# MainMaster.net
KiCad netlist of a schematic drawn in Altium Designer
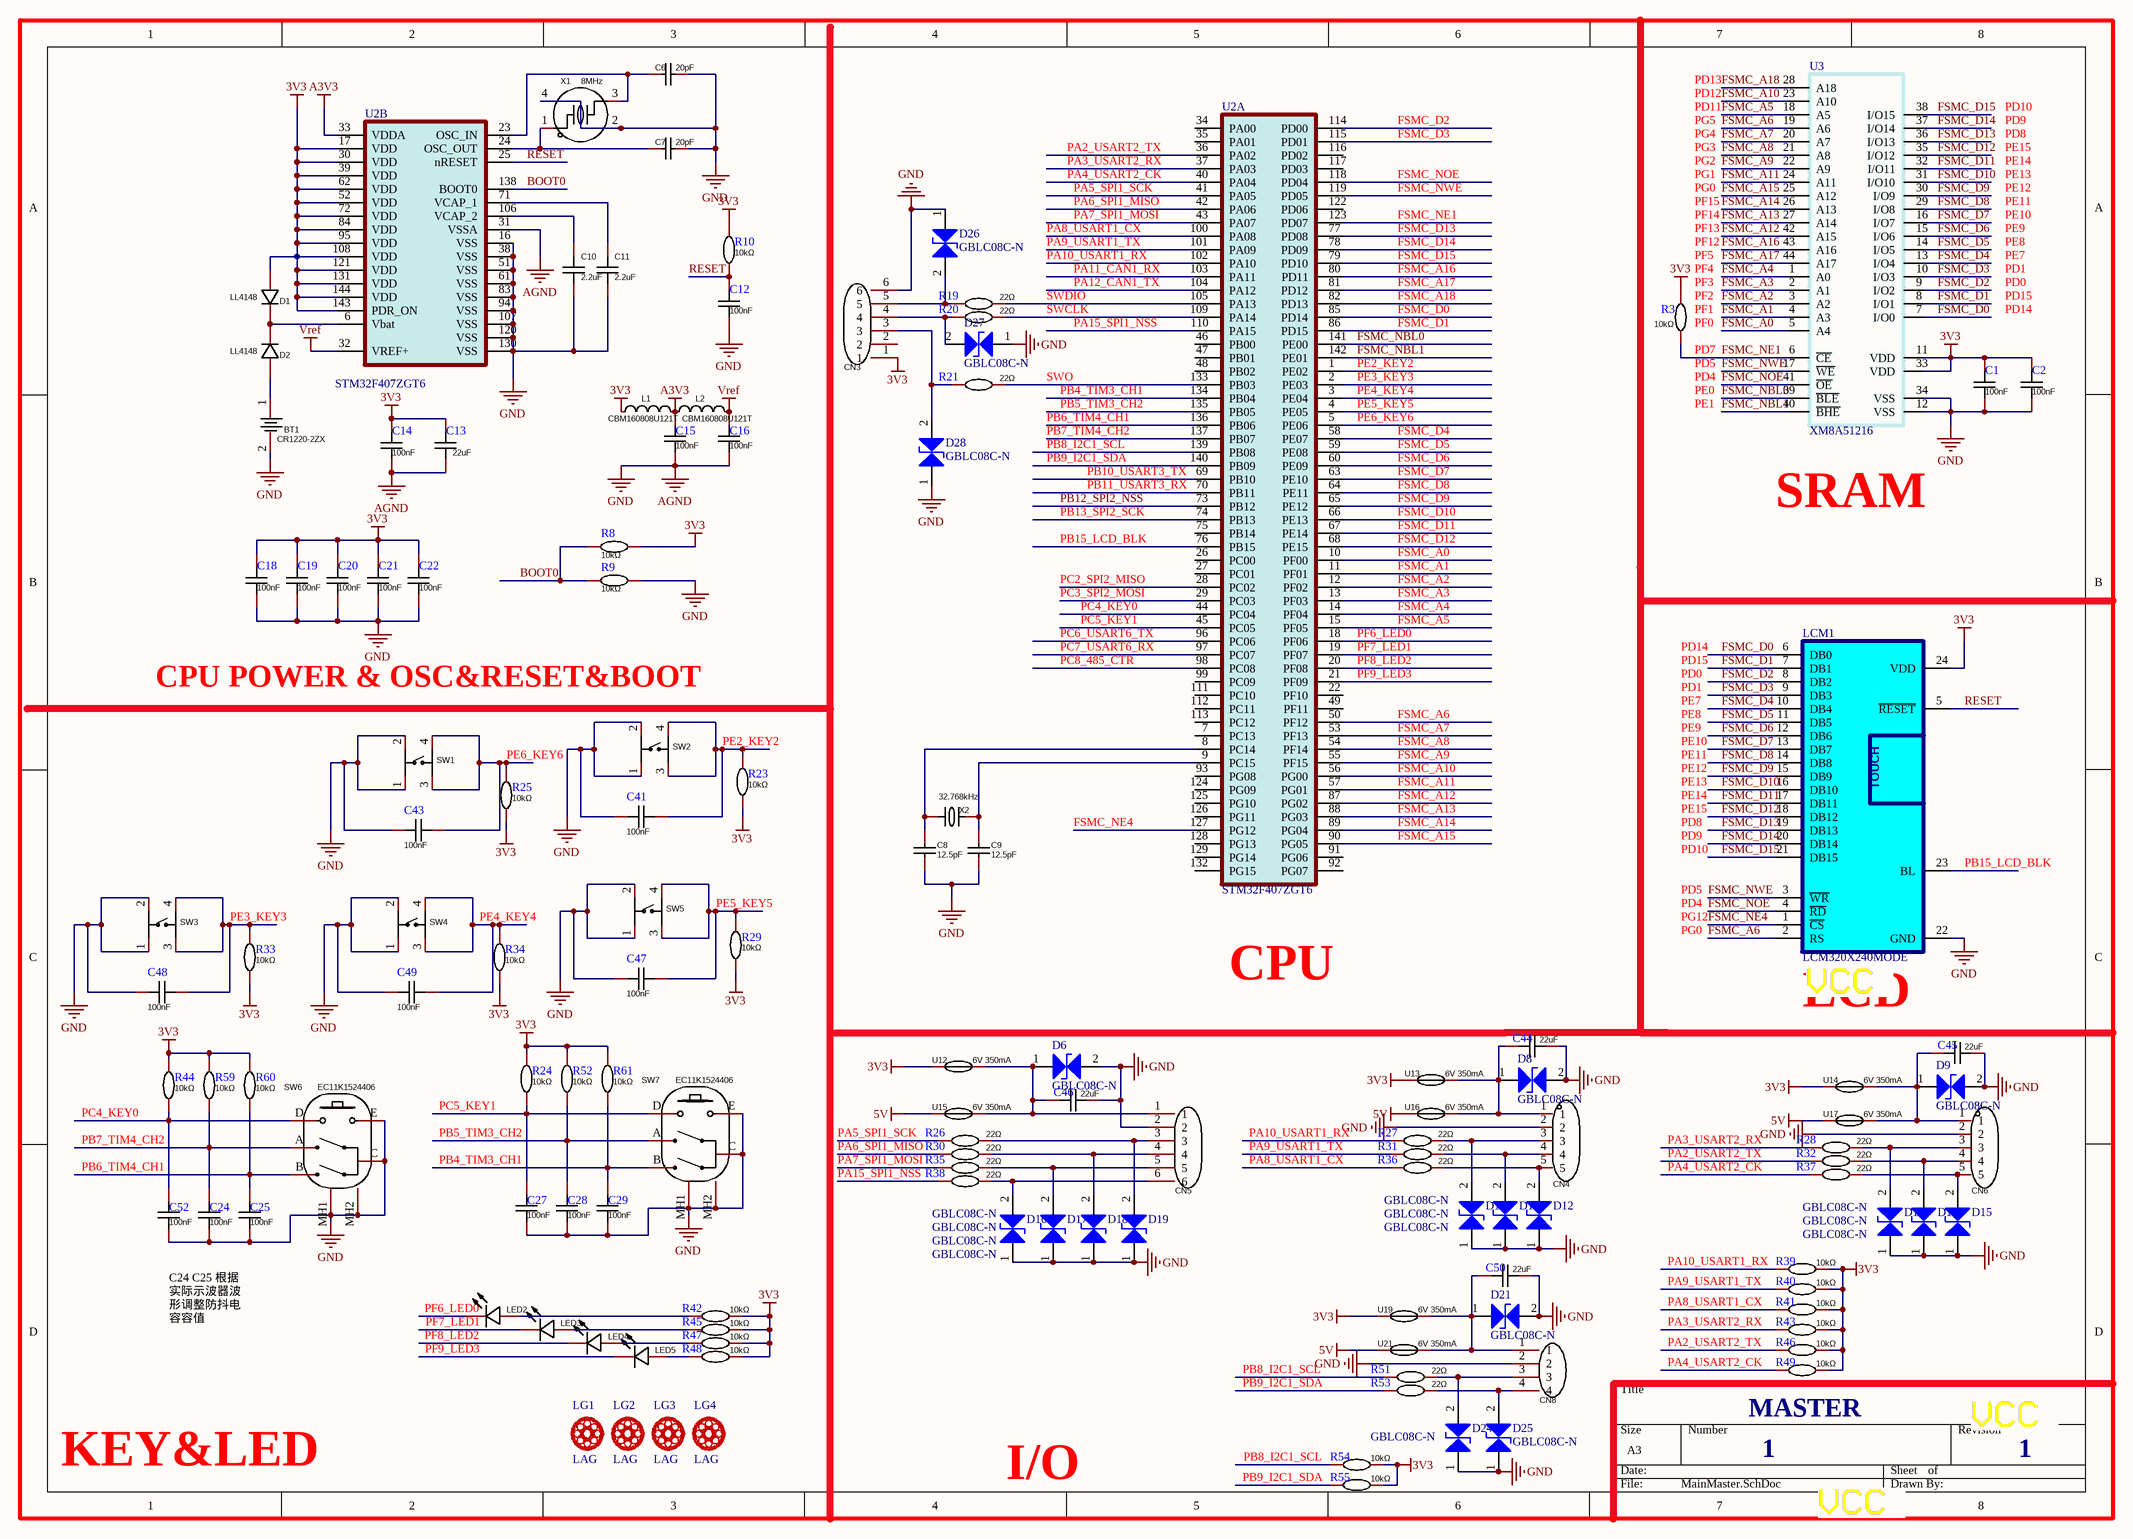
[diagram p0: MainMaster.SchDoc]

(export (version "E")
  (design (tool "Eeschema 10.0.6"))
  (components
    (comp (ref "BT1")
      (value "CR1220-2ZX")
      (footprint "LI1220_1")
      (fields (field (name "NAME") "CR1220-2ZX") (field (name "MANUFACTURER") "Q&J"))
      (libsource (lib "altium-import") (part "root_3_CR1220-2ZX_"))
    )
    (comp (ref "C1")
      (value "CC0603KRX7R9BB104")
      (footprint "C0603")
      (fields
        (field (name "NAME") "100nF")
        (field (name "MANUFACTURER") "YAGEO(国巨)")
        (field (name "TOLERANCE") "±10%")
      )
      (libsource (lib "altium-import") (part "root_1_CC0603KRX7R9BB104_"))
    )
    (comp (ref "C2")
      (value "CC0603KRX7R9BB104")
      (footprint "C0603")
      (fields
        (field (name "NAME") "100nF")
        (field (name "MANUFACTURER") "YAGEO(国巨)")
        (field (name "TOLERANCE") "±10%")
      )
      (libsource (lib "altium-import") (part "root_1_CC0603KRX7R9BB104_"))
    )
    (comp (ref "C6")
      (value "CC0603JRNPO9BN200")
      (footprint "C0603")
      (fields
        (field (name "NAME") "20pF")
        (field (name "MANUFACTURER") "YAGEO(国巨)")
        (field (name "TOLERANCE") "±5%")
      )
      (libsource (lib "altium-import") (part "root_0_CC0603JRNPO9BN200_"))
    )
    (comp (ref "C7")
      (value "CC0603JRNPO9BN200")
      (footprint "C0603")
      (fields
        (field (name "NAME") "20pF")
        (field (name "MANUFACTURER") "YAGEO(国巨)")
        (field (name "TOLERANCE") "±5%")
      )
      (libsource (lib "altium-import") (part "root_0_CC0603JRNPO9BN200_"))
    )
    (comp (ref "C8")
      (value "CC0603JRNPO9BN200")
      (footprint "C0603")
      (fields
        (field (name "NAME") "12.5pF")
        (field (name "MANUFACTURER") "YAGEO(国巨)")
        (field (name "TOLERANCE") "±5%")
      )
      (libsource (lib "altium-import") (part "root_1_CC0603JRNPO9BN200_"))
    )
    (comp (ref "C9")
      (value "CC0603JRNPO9BN200")
      (footprint "C0603")
      (fields
        (field (name "NAME") "12.5pF")
        (field (name "MANUFACTURER") "YAGEO(国巨)")
        (field (name "TOLERANCE") "±5%")
      )
      (libsource (lib "altium-import") (part "root_1_CC0603JRNPO9BN200_"))
    )
    (comp (ref "C10")
      (value "CL10A225KA8NNNC")
      (footprint "C0603")
      (fields
        (field (name "NAME") "2.2uF")
        (field (name "MANUFACTURER") "SAMSUNG(三星)")
        (field (name "TOLERANCE") "±10%")
      )
      (libsource (lib "altium-import") (part "root_1_CL10A225KA8NNNC_"))
    )
    (comp (ref "C11")
      (value "CL10A225KA8NNNC")
      (footprint "C0603")
      (fields
        (field (name "NAME") "2.2uF")
        (field (name "MANUFACTURER") "SAMSUNG(三星)")
        (field (name "TOLERANCE") "±10%")
      )
      (libsource (lib "altium-import") (part "root_1_CL10A225KA8NNNC_"))
    )
    (comp (ref "C12")
      (value "CC0603KRX7R9BB104")
      (footprint "C0603")
      (fields
        (field (name "NAME") "100nF")
        (field (name "MANUFACTURER") "YAGEO(国巨)")
        (field (name "TOLERANCE") "±10%")
      )
      (libsource (lib "altium-import") (part "root_1_CC0603KRX7R9BB104_"))
    )
    (comp (ref "C13")
      (value "CC0603KRX7R9BB104")
      (footprint "C1210")
      (fields
        (field (name "NAME") "22uF")
        (field (name "MANUFACTURER") "YAGEO(国巨)")
        (field (name "TOLERANCE") "±10%")
      )
      (libsource (lib "altium-import") (part "root_1_CC0603KRX7R9BB104_"))
    )
    (comp (ref "C14")
      (value "CC0603KRX7R9BB104")
      (footprint "C0603")
      (fields
        (field (name "NAME") "100nF")
        (field (name "MANUFACTURER") "YAGEO(国巨)")
        (field (name "TOLERANCE") "±10%")
      )
      (libsource (lib "altium-import") (part "root_1_CC0603KRX7R9BB104_"))
    )
    (comp (ref "C15")
      (value "CC0603KRX7R9BB104")
      (footprint "C0603")
      (fields
        (field (name "NAME") "100nF")
        (field (name "MANUFACTURER") "YAGEO(国巨)")
        (field (name "TOLERANCE") "±10%")
      )
      (libsource (lib "altium-import") (part "root_1_CC0603KRX7R9BB104_"))
    )
    (comp (ref "C16")
      (value "CC0603KRX7R9BB104")
      (footprint "C0603")
      (fields
        (field (name "NAME") "100nF")
        (field (name "MANUFACTURER") "YAGEO(国巨)")
        (field (name "TOLERANCE") "±10%")
      )
      (libsource (lib "altium-import") (part "root_1_CC0603KRX7R9BB104_"))
    )
    (comp (ref "C18")
      (value "CC0603KRX7R9BB104")
      (footprint "C0603")
      (fields
        (field (name "NAME") "100nF")
        (field (name "MANUFACTURER") "YAGEO(国巨)")
        (field (name "TOLERANCE") "±10%")
      )
      (libsource (lib "altium-import") (part "root_1_CC0603KRX7R9BB104_"))
    )
    (comp (ref "C19")
      (value "CC0603KRX7R9BB104")
      (footprint "C0603")
      (fields
        (field (name "NAME") "100nF")
        (field (name "MANUFACTURER") "YAGEO(国巨)")
        (field (name "TOLERANCE") "±10%")
      )
      (libsource (lib "altium-import") (part "root_1_CC0603KRX7R9BB104_"))
    )
    (comp (ref "C20")
      (value "CC0603KRX7R9BB104")
      (footprint "C0603")
      (fields
        (field (name "NAME") "100nF")
        (field (name "MANUFACTURER") "YAGEO(国巨)")
        (field (name "TOLERANCE") "±10%")
      )
      (libsource (lib "altium-import") (part "root_1_CC0603KRX7R9BB104_"))
    )
    (comp (ref "C21")
      (value "CC0603KRX7R9BB104")
      (footprint "C0603")
      (fields
        (field (name "NAME") "100nF")
        (field (name "MANUFACTURER") "YAGEO(国巨)")
        (field (name "TOLERANCE") "±10%")
      )
      (libsource (lib "altium-import") (part "root_1_CC0603KRX7R9BB104_"))
    )
    (comp (ref "C22")
      (value "CC0603KRX7R9BB104")
      (footprint "C0603")
      (fields
        (field (name "NAME") "100nF")
        (field (name "MANUFACTURER") "YAGEO(国巨)")
        (field (name "TOLERANCE") "±10%")
      )
      (libsource (lib "altium-import") (part "root_1_CC0603KRX7R9BB104_"))
    )
    (comp (ref "C24")
      (value "CC0603KRX7R9BB104")
      (footprint "C0603")
      (fields
        (field (name "NAME") "100nF")
        (field (name "MANUFACTURER") "YAGEO(国巨)")
        (field (name "TOLERANCE") "±10%")
      )
      (libsource (lib "altium-import") (part "root_3_CC0603KRX7R9BB104_"))
    )
    (comp (ref "C25")
      (value "CC0603KRX7R9BB104")
      (footprint "C0603")
      (fields
        (field (name "NAME") "100nF")
        (field (name "MANUFACTURER") "YAGEO(国巨)")
        (field (name "TOLERANCE") "±10%")
      )
      (libsource (lib "altium-import") (part "root_3_CC0603KRX7R9BB104_"))
    )
    (comp (ref "C27")
      (value "CC0603KRX7R9BB104")
      (footprint "C0603")
      (fields
        (field (name "NAME") "100nF")
        (field (name "MANUFACTURER") "YAGEO(国巨)")
        (field (name "TOLERANCE") "±10%")
      )
      (libsource (lib "altium-import") (part "root_3_CC0603KRX7R9BB104_"))
    )
    (comp (ref "C28")
      (value "CC0603KRX7R9BB104")
      (footprint "C0603")
      (fields
        (field (name "NAME") "100nF")
        (field (name "MANUFACTURER") "YAGEO(国巨)")
        (field (name "TOLERANCE") "±10%")
      )
      (libsource (lib "altium-import") (part "root_3_CC0603KRX7R9BB104_"))
    )
    (comp (ref "C29")
      (value "CC0603KRX7R9BB104")
      (footprint "C0603")
      (fields
        (field (name "NAME") "100nF")
        (field (name "MANUFACTURER") "YAGEO(国巨)")
        (field (name "TOLERANCE") "±10%")
      )
      (libsource (lib "altium-import") (part "root_3_CC0603KRX7R9BB104_"))
    )
    (comp (ref "C41")
      (value "CC0603KRX7R9BB104")
      (footprint "C0603")
      (fields
        (field (name "NAME") "100nF")
        (field (name "MANUFACTURER") "YAGEO(国巨)")
        (field (name "TOLERANCE") "±10%")
      )
      (libsource (lib "altium-import") (part "root_2_CC0603KRX7R9BB104_"))
    )
    (comp (ref "C43")
      (value "CC0603KRX7R9BB104")
      (footprint "C0603")
      (fields
        (field (name "NAME") "100nF")
        (field (name "MANUFACTURER") "YAGEO(国巨)")
        (field (name "TOLERANCE") "±10%")
      )
      (libsource (lib "altium-import") (part "root_2_CC0603KRX7R9BB104_"))
    )
    (comp (ref "C44")
      (value "CC0603KRX7R9BB104")
      (footprint "C1210")
      (fields
        (field (name "NAME") "22uF")
        (field (name "MANUFACTURER") "YAGEO(国巨)")
        (field (name "TOLERANCE") "±10%")
      )
      (libsource (lib "altium-import") (part "root_2_CC0603KRX7R9BB104_"))
    )
    (comp (ref "C45")
      (value "CC0603KRX7R9BB104")
      (footprint "C1210")
      (fields
        (field (name "NAME") "22uF")
        (field (name "MANUFACTURER") "YAGEO(国巨)")
        (field (name "TOLERANCE") "±10%")
      )
      (libsource (lib "altium-import") (part "root_2_CC0603KRX7R9BB104_"))
    )
    (comp (ref "C46")
      (value "CC0603KRX7R9BB104")
      (footprint "C1210")
      (fields
        (field (name "NAME") "22uF")
        (field (name "MANUFACTURER") "YAGEO(国巨)")
        (field (name "TOLERANCE") "±10%")
      )
      (libsource (lib "altium-import") (part "root_2_CC0603KRX7R9BB104_"))
    )
    (comp (ref "C47")
      (value "CC0603KRX7R9BB104")
      (footprint "C0603")
      (fields
        (field (name "NAME") "100nF")
        (field (name "MANUFACTURER") "YAGEO(国巨)")
        (field (name "TOLERANCE") "±10%")
      )
      (libsource (lib "altium-import") (part "root_2_CC0603KRX7R9BB104_"))
    )
    (comp (ref "C48")
      (value "CC0603KRX7R9BB104")
      (footprint "C0603")
      (fields
        (field (name "NAME") "100nF")
        (field (name "MANUFACTURER") "YAGEO(国巨)")
        (field (name "TOLERANCE") "±10%")
      )
      (libsource (lib "altium-import") (part "root_2_CC0603KRX7R9BB104_"))
    )
    (comp (ref "C49")
      (value "CC0603KRX7R9BB104")
      (footprint "C0603")
      (fields
        (field (name "NAME") "100nF")
        (field (name "MANUFACTURER") "YAGEO(国巨)")
        (field (name "TOLERANCE") "±10%")
      )
      (libsource (lib "altium-import") (part "root_2_CC0603KRX7R9BB104_"))
    )
    (comp (ref "C50")
      (value "CC0603KRX7R9BB104")
      (footprint "C1210")
      (fields
        (field (name "NAME") "22uF")
        (field (name "MANUFACTURER") "YAGEO(国巨)")
        (field (name "TOLERANCE") "±10%")
      )
      (libsource (lib "altium-import") (part "root_2_CC0603KRX7R9BB104_"))
    )
    (comp (ref "C52")
      (value "CC0603KRX7R9BB104")
      (footprint "C0603")
      (fields
        (field (name "NAME") "100nF")
        (field (name "MANUFACTURER") "YAGEO(国巨)")
        (field (name "TOLERANCE") "±10%")
      )
      (libsource (lib "altium-import") (part "root_3_CC0603KRX7R9BB104_"))
    )
    (comp (ref "CN3")
      (value "XH-6A")
      (footprint "XH2.5-6P")
      (fields (field (name "MANUFACTURER") "BOOMELE(博穆精密)"))
      (libsource (lib "altium-import") (part "root_2_mirrored_XH-6A_"))
    )
    (comp (ref "CN4")
      (value "XH-5A")
      (footprint "XH2.5-5P")
      (fields (field (name "MANUFACTURER") "BOOMELE(博穆精密)"))
      (libsource (lib "altium-import") (part "root_0_XH-5A_"))
    )
    (comp (ref "CN5")
      (value "XH-6A")
      (footprint "XH2.5-6P")
      (fields (field (name "MANUFACTURER") "BOOMELE(博穆精密)"))
      (libsource (lib "altium-import") (part "root_0_mirrored_XH-6A_"))
    )
    (comp (ref "CN6")
      (value "XH-5A")
      (footprint "XH2.5-5P")
      (fields (field (name "MANUFACTURER") "BOOMELE(博穆精密)"))
      (libsource (lib "altium-import") (part "root_0_XH-5A_"))
    )
    (comp (ref "CN8")
      (value "XH-4A")
      (footprint "XH2.5-4P")
      (fields (field (name "MANUFACTURER") "BOOMELE(博穆精密)"))
      (libsource (lib "altium-import") (part "root_0_mirrored_XH-4A_"))
    )
    (comp (ref "D1")
      (value "LL4148_C84135")
      (footprint "MINI_MELF (LL34)")
      (fields
        (field (name "NAME") "LL4148")
        (field (name "MANUFACTURER") "onsemi(安森美)")
        (field (name "MANUFACTURER PART") "LL4148")
      )
      (libsource (lib "altium-import") (part "root_1_LL4148_C84135_"))
    )
    (comp (ref "D2")
      (value "LL4148_C84135")
      (footprint "MINI_MELF (LL34)")
      (fields
        (field (name "NAME") "LL4148")
        (field (name "MANUFACTURER") "onsemi(安森美)")
        (field (name "MANUFACTURER PART") "LL4148")
      )
      (libsource (lib "altium-import") (part "root_3_LL4148_C84135_"))
    )
    (comp (ref "D6")
      (value "GBLC08C-N")
      (footprint "SOD-323_L1.8-W1.3-LS2.5-BI")
      (description "LXES1UTAA1-157,0402,MURATA")
      (fields (field (name "NAME") "GBLC08C-N") (field (name "MANUFACTURER") "BORN伯恩半导体"))
      (libsource (lib "ErpMaterialData-U9") (part "DIODE ZENER2"))
    )
    (comp (ref "D8")
      (value "GBLC08C-N")
      (footprint "SOD-323_L1.8-W1.3-LS2.5-BI")
      (description "LXES1UTAA1-157,0402,MURATA")
      (fields (field (name "NAME") "GBLC08C-N") (field (name "MANUFACTURER") "BORN伯恩半导体"))
      (libsource (lib "ErpMaterialData-U9") (part "DIODE ZENER2"))
    )
    (comp (ref "D9")
      (value "GBLC08C-N")
      (footprint "SOD-323_L1.8-W1.3-LS2.5-BI")
      (description "LXES1UTAA1-157,0402,MURATA")
      (fields (field (name "NAME") "GBLC08C-N") (field (name "MANUFACTURER") "BORN伯恩半导体"))
      (libsource (lib "ErpMaterialData-U9") (part "DIODE ZENER2"))
    )
    (comp (ref "D10")
      (value "GBLC08C-N")
      (footprint "SOD-323_L1.8-W1.3-LS2.5-BI")
      (description "LXES1UTAA1-157,0402,MURATA")
      (fields (field (name "NAME") "GBLC08C-N") (field (name "MANUFACTURER") "BORN伯恩半导体"))
      (libsource (lib "ErpMaterialData-U9") (part "DIODE ZENER2"))
    )
    (comp (ref "D11")
      (value "GBLC08C-N")
      (footprint "SOD-323_L1.8-W1.3-LS2.5-BI")
      (description "LXES1UTAA1-157,0402,MURATA")
      (fields (field (name "NAME") "GBLC08C-N") (field (name "MANUFACTURER") "BORN伯恩半导体"))
      (libsource (lib "ErpMaterialData-U9") (part "DIODE ZENER2"))
    )
    (comp (ref "D12")
      (value "GBLC08C-N")
      (footprint "SOD-323_L1.8-W1.3-LS2.5-BI")
      (description "LXES1UTAA1-157,0402,MURATA")
      (fields (field (name "NAME") "GBLC08C-N") (field (name "MANUFACTURER") "BORN伯恩半导体"))
      (libsource (lib "ErpMaterialData-U9") (part "DIODE ZENER2"))
    )
    (comp (ref "D13")
      (value "GBLC08C-N")
      (footprint "SOD-323_L1.8-W1.3-LS2.5-BI")
      (description "LXES1UTAA1-157,0402,MURATA")
      (fields (field (name "NAME") "GBLC08C-N") (field (name "MANUFACTURER") "BORN伯恩半导体"))
      (libsource (lib "ErpMaterialData-U9") (part "DIODE ZENER2"))
    )
    (comp (ref "D14")
      (value "GBLC08C-N")
      (footprint "SOD-323_L1.8-W1.3-LS2.5-BI")
      (description "LXES1UTAA1-157,0402,MURATA")
      (fields (field (name "NAME") "GBLC08C-N") (field (name "MANUFACTURER") "BORN伯恩半导体"))
      (libsource (lib "ErpMaterialData-U9") (part "DIODE ZENER2"))
    )
    (comp (ref "D15")
      (value "GBLC08C-N")
      (footprint "SOD-323_L1.8-W1.3-LS2.5-BI")
      (description "LXES1UTAA1-157,0402,MURATA")
      (fields (field (name "NAME") "GBLC08C-N") (field (name "MANUFACTURER") "BORN伯恩半导体"))
      (libsource (lib "ErpMaterialData-U9") (part "DIODE ZENER2"))
    )
    (comp (ref "D16")
      (value "GBLC08C-N")
      (footprint "SOD-323_L1.8-W1.3-LS2.5-BI")
      (description "LXES1UTAA1-157,0402,MURATA")
      (fields (field (name "NAME") "GBLC08C-N") (field (name "MANUFACTURER") "BORN伯恩半导体"))
      (libsource (lib "ErpMaterialData-U9") (part "DIODE ZENER2"))
    )
    (comp (ref "D17")
      (value "GBLC08C-N")
      (footprint "SOD-323_L1.8-W1.3-LS2.5-BI")
      (description "LXES1UTAA1-157,0402,MURATA")
      (fields (field (name "NAME") "GBLC08C-N") (field (name "MANUFACTURER") "BORN伯恩半导体"))
      (libsource (lib "ErpMaterialData-U9") (part "DIODE ZENER2"))
    )
    (comp (ref "D18")
      (value "GBLC08C-N")
      (footprint "SOD-323_L1.8-W1.3-LS2.5-BI")
      (description "LXES1UTAA1-157,0402,MURATA")
      (fields (field (name "NAME") "GBLC08C-N") (field (name "MANUFACTURER") "BORN伯恩半导体"))
      (libsource (lib "ErpMaterialData-U9") (part "DIODE ZENER2"))
    )
    (comp (ref "D19")
      (value "GBLC08C-N")
      (footprint "SOD-323_L1.8-W1.3-LS2.5-BI")
      (description "LXES1UTAA1-157,0402,MURATA")
      (fields (field (name "NAME") "GBLC08C-N") (field (name "MANUFACTURER") "BORN伯恩半导体"))
      (libsource (lib "ErpMaterialData-U9") (part "DIODE ZENER2"))
    )
    (comp (ref "D21")
      (value "GBLC08C-N")
      (footprint "SOD-323_L1.8-W1.3-LS2.5-BI")
      (description "LXES1UTAA1-157,0402,MURATA")
      (fields (field (name "NAME") "GBLC08C-N") (field (name "MANUFACTURER") "BORN伯恩半导体"))
      (libsource (lib "ErpMaterialData-U9") (part "DIODE ZENER2"))
    )
    (comp (ref "D24")
      (value "GBLC08C-N")
      (footprint "SOD-323_L1.8-W1.3-LS2.5-BI")
      (description "LXES1UTAA1-157,0402,MURATA")
      (fields (field (name "NAME") "GBLC08C-N") (field (name "MANUFACTURER") "BORN伯恩半导体"))
      (libsource (lib "ErpMaterialData-U9") (part "DIODE ZENER2"))
    )
    (comp (ref "D25")
      (value "GBLC08C-N")
      (footprint "SOD-323_L1.8-W1.3-LS2.5-BI")
      (description "LXES1UTAA1-157,0402,MURATA")
      (fields (field (name "NAME") "GBLC08C-N") (field (name "MANUFACTURER") "BORN伯恩半导体"))
      (libsource (lib "ErpMaterialData-U9") (part "DIODE ZENER2"))
    )
    (comp (ref "D26")
      (value "GBLC08C-N")
      (footprint "SOD-323_L1.8-W1.3-LS2.5-BI")
      (description "LXES1UTAA1-157,0402,MURATA")
      (fields (field (name "NAME") "GBLC08C-N") (field (name "MANUFACTURER") "BORN伯恩半导体"))
      (libsource (lib "ErpMaterialData-U9") (part "DIODE ZENER2"))
    )
    (comp (ref "D27")
      (value "GBLC08C-N")
      (footprint "SOD-323_L1.8-W1.3-LS2.5-BI")
      (description "LXES1UTAA1-157,0402,MURATA")
      (fields (field (name "NAME") "GBLC08C-N") (field (name "MANUFACTURER") "BORN伯恩半导体"))
      (libsource (lib "ErpMaterialData-U9") (part "DIODE ZENER2"))
    )
    (comp (ref "D28")
      (value "GBLC08C-N")
      (footprint "SOD-323_L1.8-W1.3-LS2.5-BI")
      (description "LXES1UTAA1-157,0402,MURATA")
      (fields (field (name "NAME") "GBLC08C-N") (field (name "MANUFACTURER") "BORN伯恩半导体"))
      (libsource (lib "ErpMaterialData-U9") (part "DIODE ZENER2"))
    )
    (comp (ref "L1")
      (value "CBM160808U121T")
      (footprint "L0603")
      (fields
        (field (name "NAME") "CBM160808U121T")
        (field (name "MANUFACTURER") "FH(风华)")
        (field (name "TOLERANCE") "±25%")
      )
      (libsource (lib "altium-import") (part "root_0_CBM160808U121T_"))
    )
    (comp (ref "L2")
      (value "CBM160808U121T")
      (footprint "L0603")
      (fields
        (field (name "NAME") "CBM160808U121T")
        (field (name "MANUFACTURER") "FH(风华)")
        (field (name "TOLERANCE") "±25%")
      )
      (libsource (lib "altium-import") (part "root_0_CBM160808U121T_"))
    )
    (comp (ref "LCM1")
      (value "LCM320X240MODE")
      (footprint "LCM2.8 MODE")
      (libsource (lib "华南师范控制板") (part "LCM320X240MODE"))
    )
    (comp (ref "LED2")
      (value "17-21SYGC/S530-E3/TR8")
      (footprint "LED 0805G")
      (fields (field (name "MANUFACTURER") "EVERLIGHT(亿光)"))
      (libsource (lib "altium-import") (part "root_0_17-21SYGC/S530-E3/TR8_"))
    )
    (comp (ref "LED3")
      (value "17-21SYGC/S530-E3/TR8")
      (footprint "LED 0805G")
      (fields (field (name "MANUFACTURER") "EVERLIGHT(亿光)"))
      (libsource (lib "altium-import") (part "root_0_17-21SYGC/S530-E3/TR8_"))
    )
    (comp (ref "LED4")
      (value "17-21SYGC/S530-E3/TR8")
      (footprint "LED 0805G")
      (fields (field (name "MANUFACTURER") "EVERLIGHT(亿光)"))
      (libsource (lib "altium-import") (part "root_0_17-21SYGC/S530-E3/TR8_"))
    )
    (comp (ref "LED5")
      (value "17-21SYGC/S530-E3/TR8")
      (footprint "LED 0805G")
      (fields (field (name "MANUFACTURER") "EVERLIGHT(亿光)"))
      (libsource (lib "altium-import") (part "root_0_17-21SYGC/S530-E3/TR8_"))
    )
    (comp (ref "LG1") (value "LAG") (footprint "LAGVAL") (libsource (lib "3DGeneral") (part "LAGVAL")))
    (comp (ref "LG2") (value "LAG") (footprint "LAGVAL") (libsource (lib "3DGeneral") (part "LAGVAL")))
    (comp (ref "LG3") (value "LAG") (footprint "LAGVAL") (libsource (lib "3DGeneral") (part "LAGVAL")))
    (comp (ref "LG4") (value "LAG") (footprint "LAGVAL") (libsource (lib "3DGeneral") (part "LAGVAL")))
    (comp (ref "R3")
      (value "10kΩ")
      (footprint "R0603")
      (fields
        (field (name "MANUFACTURER") "UNI-ROYAL(厚声)")
        (field (name "MANUFACTURER PART") "0603WAF5113T5E")
        (field (name "TOLERANCE") "±1%")
      )
      (libsource (lib "altium-import") (part "root_1_0603WAF5113T5E_"))
    )
    (comp (ref "R8")
      (value "10kΩ")
      (footprint "R0603")
      (fields
        (field (name "MANUFACTURER") "UNI-ROYAL(厚声)")
        (field (name "MANUFACTURER PART") "0603WAF5113T5E")
        (field (name "TOLERANCE") "±1%")
      )
      (libsource (lib "altium-import") (part "root_0_0603WAF5113T5E_"))
    )
    (comp (ref "R9")
      (value "10kΩ")
      (footprint "R0603")
      (fields
        (field (name "MANUFACTURER") "UNI-ROYAL(厚声)")
        (field (name "MANUFACTURER PART") "0603WAF5113T5E")
        (field (name "TOLERANCE") "±1%")
      )
      (libsource (lib "altium-import") (part "root_0_0603WAF5113T5E_"))
    )
    (comp (ref "R10")
      (value "10kΩ")
      (footprint "R0603")
      (fields
        (field (name "MANUFACTURER") "UNI-ROYAL(厚声)")
        (field (name "MANUFACTURER PART") "0603WAF5113T5E")
        (field (name "TOLERANCE") "±1%")
      )
      (libsource (lib "altium-import") (part "root_3_0603WAF5113T5E_"))
    )
    (comp (ref "R19")
      (value "22Ω")
      (footprint "R0603")
      (fields
        (field (name "MANUFACTURER") "UNI-ROYAL(厚声)")
        (field (name "MANUFACTURER PART") "0603WAF5113T5E")
        (field (name "TOLERANCE") "±1%")
      )
      (libsource (lib "altium-import") (part "root_2_0603WAF5113T5E_"))
    )
    (comp (ref "R20")
      (value "22Ω")
      (footprint "R0603")
      (fields
        (field (name "MANUFACTURER") "UNI-ROYAL(厚声)")
        (field (name "MANUFACTURER PART") "0603WAF5113T5E")
        (field (name "TOLERANCE") "±1%")
      )
      (libsource (lib "altium-import") (part "root_2_0603WAF5113T5E_"))
    )
    (comp (ref "R21")
      (value "22Ω")
      (footprint "R0603")
      (fields
        (field (name "MANUFACTURER") "UNI-ROYAL(厚声)")
        (field (name "MANUFACTURER PART") "0603WAF5113T5E")
        (field (name "TOLERANCE") "±1%")
      )
      (libsource (lib "altium-import") (part "root_2_0603WAF5113T5E_"))
    )
    (comp (ref "R23")
      (value "10kΩ")
      (footprint "R0603")
      (fields
        (field (name "MANUFACTURER") "UNI-ROYAL(厚声)")
        (field (name "MANUFACTURER PART") "0603WAF5113T5E")
        (field (name "TOLERANCE") "±1%")
      )
      (libsource (lib "altium-import") (part "root_1_0603WAF5113T5E_"))
    )
    (comp (ref "R24")
      (value "10kΩ")
      (footprint "R0603")
      (fields
        (field (name "MANUFACTURER") "UNI-ROYAL(厚声)")
        (field (name "MANUFACTURER PART") "0603WAF5113T5E")
        (field (name "TOLERANCE") "±1%")
      )
      (libsource (lib "altium-import") (part "root_1_0603WAF5113T5E_"))
    )
    (comp (ref "R25")
      (value "10kΩ")
      (footprint "R0603")
      (fields
        (field (name "MANUFACTURER") "UNI-ROYAL(厚声)")
        (field (name "MANUFACTURER PART") "0603WAF5113T5E")
        (field (name "TOLERANCE") "±1%")
      )
      (libsource (lib "altium-import") (part "root_1_0603WAF5113T5E_"))
    )
    (comp (ref "R26")
      (value "22Ω")
      (footprint "R0603")
      (fields
        (field (name "MANUFACTURER") "UNI-ROYAL(厚声)")
        (field (name "MANUFACTURER PART") "0603WAF5113T5E")
        (field (name "TOLERANCE") "±1%")
      )
      (libsource (lib "altium-import") (part "root_2_0603WAF5113T5E_"))
    )
    (comp (ref "R27")
      (value "22Ω")
      (footprint "R0603")
      (fields
        (field (name "MANUFACTURER") "UNI-ROYAL(厚声)")
        (field (name "MANUFACTURER PART") "0603WAF5113T5E")
        (field (name "TOLERANCE") "±1%")
      )
      (libsource (lib "altium-import") (part "root_2_0603WAF5113T5E_"))
    )
    (comp (ref "R28")
      (value "22Ω")
      (footprint "R0603")
      (fields
        (field (name "MANUFACTURER") "UNI-ROYAL(厚声)")
        (field (name "MANUFACTURER PART") "0603WAF5113T5E")
        (field (name "TOLERANCE") "±1%")
      )
      (libsource (lib "altium-import") (part "root_2_0603WAF5113T5E_"))
    )
    (comp (ref "R29")
      (value "10kΩ")
      (footprint "R0603")
      (fields
        (field (name "MANUFACTURER") "UNI-ROYAL(厚声)")
        (field (name "MANUFACTURER PART") "0603WAF5113T5E")
        (field (name "TOLERANCE") "±1%")
      )
      (libsource (lib "altium-import") (part "root_1_0603WAF5113T5E_"))
    )
    (comp (ref "R30")
      (value "22Ω")
      (footprint "R0603")
      (fields
        (field (name "MANUFACTURER") "UNI-ROYAL(厚声)")
        (field (name "MANUFACTURER PART") "0603WAF5113T5E")
        (field (name "TOLERANCE") "±1%")
      )
      (libsource (lib "altium-import") (part "root_2_0603WAF5113T5E_"))
    )
    (comp (ref "R31")
      (value "22Ω")
      (footprint "R0603")
      (fields
        (field (name "MANUFACTURER") "UNI-ROYAL(厚声)")
        (field (name "MANUFACTURER PART") "0603WAF5113T5E")
        (field (name "TOLERANCE") "±1%")
      )
      (libsource (lib "altium-import") (part "root_2_0603WAF5113T5E_"))
    )
    (comp (ref "R32")
      (value "22Ω")
      (footprint "R0603")
      (fields
        (field (name "MANUFACTURER") "UNI-ROYAL(厚声)")
        (field (name "MANUFACTURER PART") "0603WAF5113T5E")
        (field (name "TOLERANCE") "±1%")
      )
      (libsource (lib "altium-import") (part "root_2_0603WAF5113T5E_"))
    )
    (comp (ref "R33")
      (value "10kΩ")
      (footprint "R0603")
      (fields
        (field (name "MANUFACTURER") "UNI-ROYAL(厚声)")
        (field (name "MANUFACTURER PART") "0603WAF5113T5E")
        (field (name "TOLERANCE") "±1%")
      )
      (libsource (lib "altium-import") (part "root_1_0603WAF5113T5E_"))
    )
    (comp (ref "R34")
      (value "10kΩ")
      (footprint "R0603")
      (fields
        (field (name "MANUFACTURER") "UNI-ROYAL(厚声)")
        (field (name "MANUFACTURER PART") "0603WAF5113T5E")
        (field (name "TOLERANCE") "±1%")
      )
      (libsource (lib "altium-import") (part "root_1_0603WAF5113T5E_"))
    )
    (comp (ref "R35")
      (value "22Ω")
      (footprint "R0603")
      (fields
        (field (name "MANUFACTURER") "UNI-ROYAL(厚声)")
        (field (name "MANUFACTURER PART") "0603WAF5113T5E")
        (field (name "TOLERANCE") "±1%")
      )
      (libsource (lib "altium-import") (part "root_2_0603WAF5113T5E_"))
    )
    (comp (ref "R36")
      (value "22Ω")
      (footprint "R0603")
      (fields
        (field (name "MANUFACTURER") "UNI-ROYAL(厚声)")
        (field (name "MANUFACTURER PART") "0603WAF5113T5E")
        (field (name "TOLERANCE") "±1%")
      )
      (libsource (lib "altium-import") (part "root_2_0603WAF5113T5E_"))
    )
    (comp (ref "R37")
      (value "22Ω")
      (footprint "R0603")
      (fields
        (field (name "MANUFACTURER") "UNI-ROYAL(厚声)")
        (field (name "MANUFACTURER PART") "0603WAF5113T5E")
        (field (name "TOLERANCE") "±1%")
      )
      (libsource (lib "altium-import") (part "root_2_0603WAF5113T5E_"))
    )
    (comp (ref "R38")
      (value "22Ω")
      (footprint "R0603")
      (fields
        (field (name "MANUFACTURER") "UNI-ROYAL(厚声)")
        (field (name "MANUFACTURER PART") "0603WAF5113T5E")
        (field (name "TOLERANCE") "±1%")
      )
      (libsource (lib "altium-import") (part "root_2_0603WAF5113T5E_"))
    )
    (comp (ref "R39")
      (value "10kΩ")
      (footprint "R0603")
      (fields
        (field (name "MANUFACTURER") "UNI-ROYAL(厚声)")
        (field (name "MANUFACTURER PART") "0603WAF5113T5E")
        (field (name "TOLERANCE") "±1%")
      )
      (libsource (lib "altium-import") (part "root_2_0603WAF5113T5E_"))
    )
    (comp (ref "R40")
      (value "10kΩ")
      (footprint "R0603")
      (fields
        (field (name "MANUFACTURER") "UNI-ROYAL(厚声)")
        (field (name "MANUFACTURER PART") "0603WAF5113T5E")
        (field (name "TOLERANCE") "±1%")
      )
      (libsource (lib "altium-import") (part "root_2_0603WAF5113T5E_"))
    )
    (comp (ref "R41")
      (value "10kΩ")
      (footprint "R0603")
      (fields
        (field (name "MANUFACTURER") "UNI-ROYAL(厚声)")
        (field (name "MANUFACTURER PART") "0603WAF5113T5E")
        (field (name "TOLERANCE") "±1%")
      )
      (libsource (lib "altium-import") (part "root_2_0603WAF5113T5E_"))
    )
    (comp (ref "R42")
      (value "10kΩ")
      (footprint "R0603")
      (fields
        (field (name "MANUFACTURER") "UNI-ROYAL(厚声)")
        (field (name "MANUFACTURER PART") "0603WAF5113T5E")
        (field (name "TOLERANCE") "±1%")
      )
      (libsource (lib "altium-import") (part "root_2_0603WAF5113T5E_"))
    )
    (comp (ref "R43")
      (value "10kΩ")
      (footprint "R0603")
      (fields
        (field (name "MANUFACTURER") "UNI-ROYAL(厚声)")
        (field (name "MANUFACTURER PART") "0603WAF5113T5E")
        (field (name "TOLERANCE") "±1%")
      )
      (libsource (lib "altium-import") (part "root_2_0603WAF5113T5E_"))
    )
    (comp (ref "R44")
      (value "10kΩ")
      (footprint "R0603")
      (fields
        (field (name "MANUFACTURER") "UNI-ROYAL(厚声)")
        (field (name "MANUFACTURER PART") "0603WAF5113T5E")
        (field (name "TOLERANCE") "±1%")
      )
      (libsource (lib "altium-import") (part "root_1_0603WAF5113T5E_"))
    )
    (comp (ref "R45")
      (value "10kΩ")
      (footprint "R0603")
      (fields
        (field (name "MANUFACTURER") "UNI-ROYAL(厚声)")
        (field (name "MANUFACTURER PART") "0603WAF5113T5E")
        (field (name "TOLERANCE") "±1%")
      )
      (libsource (lib "altium-import") (part "root_2_0603WAF5113T5E_"))
    )
    (comp (ref "R46")
      (value "10kΩ")
      (footprint "R0603")
      (fields
        (field (name "MANUFACTURER") "UNI-ROYAL(厚声)")
        (field (name "MANUFACTURER PART") "0603WAF5113T5E")
        (field (name "TOLERANCE") "±1%")
      )
      (libsource (lib "altium-import") (part "root_2_0603WAF5113T5E_"))
    )
    (comp (ref "R47")
      (value "10kΩ")
      (footprint "R0603")
      (fields
        (field (name "MANUFACTURER") "UNI-ROYAL(厚声)")
        (field (name "MANUFACTURER PART") "0603WAF5113T5E")
        (field (name "TOLERANCE") "±1%")
      )
      (libsource (lib "altium-import") (part "root_2_0603WAF5113T5E_"))
    )
    (comp (ref "R48")
      (value "10kΩ")
      (footprint "R0603")
      (fields
        (field (name "MANUFACTURER") "UNI-ROYAL(厚声)")
        (field (name "MANUFACTURER PART") "0603WAF5113T5E")
        (field (name "TOLERANCE") "±1%")
      )
      (libsource (lib "altium-import") (part "root_2_0603WAF5113T5E_"))
    )
    (comp (ref "R49")
      (value "10kΩ")
      (footprint "R0603")
      (fields
        (field (name "MANUFACTURER") "UNI-ROYAL(厚声)")
        (field (name "MANUFACTURER PART") "0603WAF5113T5E")
        (field (name "TOLERANCE") "±1%")
      )
      (libsource (lib "altium-import") (part "root_2_0603WAF5113T5E_"))
    )
    (comp (ref "R51")
      (value "22Ω")
      (footprint "R0603")
      (fields
        (field (name "MANUFACTURER") "UNI-ROYAL(厚声)")
        (field (name "MANUFACTURER PART") "0603WAF5113T5E")
        (field (name "TOLERANCE") "±1%")
      )
      (libsource (lib "altium-import") (part "root_2_0603WAF5113T5E_"))
    )
    (comp (ref "R52")
      (value "10kΩ")
      (footprint "R0603")
      (fields
        (field (name "MANUFACTURER") "UNI-ROYAL(厚声)")
        (field (name "MANUFACTURER PART") "0603WAF5113T5E")
        (field (name "TOLERANCE") "±1%")
      )
      (libsource (lib "altium-import") (part "root_1_0603WAF5113T5E_"))
    )
    (comp (ref "R53")
      (value "22Ω")
      (footprint "R0603")
      (fields
        (field (name "MANUFACTURER") "UNI-ROYAL(厚声)")
        (field (name "MANUFACTURER PART") "0603WAF5113T5E")
        (field (name "TOLERANCE") "±1%")
      )
      (libsource (lib "altium-import") (part "root_2_0603WAF5113T5E_"))
    )
    (comp (ref "R54")
      (value "10kΩ")
      (footprint "R0603")
      (fields
        (field (name "MANUFACTURER") "UNI-ROYAL(厚声)")
        (field (name "MANUFACTURER PART") "0603WAF5113T5E")
        (field (name "TOLERANCE") "±1%")
      )
      (libsource (lib "altium-import") (part "root_2_0603WAF5113T5E_"))
    )
    (comp (ref "R55")
      (value "10kΩ")
      (footprint "R0603")
      (fields
        (field (name "MANUFACTURER") "UNI-ROYAL(厚声)")
        (field (name "MANUFACTURER PART") "0603WAF5113T5E")
        (field (name "TOLERANCE") "±1%")
      )
      (libsource (lib "altium-import") (part "root_2_0603WAF5113T5E_"))
    )
    (comp (ref "R59")
      (value "10kΩ")
      (footprint "R0603")
      (fields
        (field (name "MANUFACTURER") "UNI-ROYAL(厚声)")
        (field (name "MANUFACTURER PART") "0603WAF5113T5E")
        (field (name "TOLERANCE") "±1%")
      )
      (libsource (lib "altium-import") (part "root_1_0603WAF5113T5E_"))
    )
    (comp (ref "R60")
      (value "10kΩ")
      (footprint "R0603")
      (fields
        (field (name "MANUFACTURER") "UNI-ROYAL(厚声)")
        (field (name "MANUFACTURER PART") "0603WAF5113T5E")
        (field (name "TOLERANCE") "±1%")
      )
      (libsource (lib "altium-import") (part "root_1_0603WAF5113T5E_"))
    )
    (comp (ref "R61")
      (value "10kΩ")
      (footprint "R0603")
      (fields
        (field (name "MANUFACTURER") "UNI-ROYAL(厚声)")
        (field (name "MANUFACTURER PART") "0603WAF5113T5E")
        (field (name "TOLERANCE") "±1%")
      )
      (libsource (lib "altium-import") (part "root_1_0603WAF5113T5E_"))
    )
    (comp (ref "SW1")
      (value "KH-6X6X5H-STM")
      (footprint "TSW DIP-12*12*7")
      (fields (field (name "MANUFACTURER") "kinghelm(金航标)"))
      (libsource (lib "altium-import") (part "root_1_KH-6X6X5H-STM_"))
    )
    (comp (ref "SW2")
      (value "KH-6X6X5H-STM")
      (footprint "TSW DIP-12*12*7")
      (fields (field (name "MANUFACTURER") "kinghelm(金航标)"))
      (libsource (lib "altium-import") (part "root_1_KH-6X6X5H-STM_"))
    )
    (comp (ref "SW3")
      (value "KH-6X6X5H-STM")
      (footprint "TSW DIP-12*12*7")
      (fields (field (name "MANUFACTURER") "kinghelm(金航标)"))
      (libsource (lib "altium-import") (part "root_1_KH-6X6X5H-STM_"))
    )
    (comp (ref "SW4")
      (value "KH-6X6X5H-STM")
      (footprint "TSW DIP-12*12*7")
      (fields (field (name "MANUFACTURER") "kinghelm(金航标)"))
      (libsource (lib "altium-import") (part "root_1_KH-6X6X5H-STM_"))
    )
    (comp (ref "SW5")
      (value "KH-6X6X5H-STM")
      (footprint "TSW DIP-12*12*7")
      (fields (field (name "MANUFACTURER") "kinghelm(金航标)"))
      (libsource (lib "altium-import") (part "root_1_KH-6X6X5H-STM_"))
    )
    (comp (ref "SW6")
      (value "EC11K1524406")
      (footprint "SW-TH_EC11K1524406")
      (fields (field (name "NAME") "EC11K1524406") (field (name "MANUFACTURER") "ALPSALPINE(阿尔卑斯阿尔派)"))
      (libsource (lib "altium-import") (part "root_0_EC11K1524406_"))
    )
    (comp (ref "SW7")
      (value "EC11K1524406")
      (footprint "SW-TH_EC11K1524406")
      (fields (field (name "NAME") "EC11K1524406") (field (name "MANUFACTURER") "ALPSALPINE(阿尔卑斯阿尔派)"))
      (libsource (lib "altium-import") (part "root_0_EC11K1524406_"))
    )
    (comp (ref "U2")
      (value "STM32F407ZGT6")
      (footprint "STM32F407ZET6_TQFP144")
      (description "STM32F407ZET6")
      (fields (field (name "MANUFACTURER") "ST(意法半导体)") (field (name "NAME") "STM32F407ZGT6"))
      (libsource (lib "") (part "STM32F407ZET6_1"))
    )
    (comp (ref "U3")
      (value "XM8A51216")
      (footprint "IS62WV51216BLL_TSOP44")
      (libsource (lib "PCB_Project") (part "IS64WV51216BLL-10MA3"))
    )
    (comp (ref "U12")
      (value "0603L035YR")
      (footprint "F0603")
      (fields (field (name "LCSC PART NAME") "6V 350mA") (field (name "MANUFACTURER") "Littelfuse(美国力特)"))
      (libsource (lib "altium-import") (part "root_0_0603L035YR_"))
    )
    (comp (ref "U13")
      (value "0603L035YR")
      (footprint "F0603")
      (fields (field (name "LCSC PART NAME") "6V 350mA") (field (name "MANUFACTURER") "Littelfuse(美国力特)"))
      (libsource (lib "altium-import") (part "root_0_0603L035YR_"))
    )
    (comp (ref "U14")
      (value "0603L035YR")
      (footprint "F0603")
      (fields (field (name "LCSC PART NAME") "6V 350mA") (field (name "MANUFACTURER") "Littelfuse(美国力特)"))
      (libsource (lib "altium-import") (part "root_0_0603L035YR_"))
    )
    (comp (ref "U15")
      (value "0603L035YR")
      (footprint "F0603")
      (fields (field (name "LCSC PART NAME") "6V 350mA") (field (name "MANUFACTURER") "Littelfuse(美国力特)"))
      (libsource (lib "altium-import") (part "root_0_0603L035YR_"))
    )
    (comp (ref "U16")
      (value "0603L035YR")
      (footprint "F0603")
      (fields (field (name "LCSC PART NAME") "6V 350mA") (field (name "MANUFACTURER") "Littelfuse(美国力特)"))
      (libsource (lib "altium-import") (part "root_0_0603L035YR_"))
    )
    (comp (ref "U17")
      (value "0603L035YR")
      (footprint "F0603")
      (fields (field (name "LCSC PART NAME") "6V 350mA") (field (name "MANUFACTURER") "Littelfuse(美国力特)"))
      (libsource (lib "altium-import") (part "root_0_0603L035YR_"))
    )
    (comp (ref "U19")
      (value "0603L035YR")
      (footprint "F0603")
      (fields (field (name "LCSC PART NAME") "6V 350mA") (field (name "MANUFACTURER") "Littelfuse(美国力特)"))
      (libsource (lib "altium-import") (part "root_0_0603L035YR_"))
    )
    (comp (ref "U21")
      (value "0603L035YR")
      (footprint "F0603")
      (fields (field (name "LCSC PART NAME") "6V 350mA") (field (name "MANUFACTURER") "Littelfuse(美国力特)"))
      (libsource (lib "altium-import") (part "root_0_0603L035YR_"))
    )
    (comp (ref "X1")
      (value "X32258MSB4SI")
      (footprint "OSC 3225-4P")
      (fields (field (name "NAME") "8MHz") (field (name "MANUFACTURER") "YXC(扬兴晶振)"))
      (libsource (lib "altium-import") (part "root_0_X32258MSB4SI_"))
    )
    (comp (ref "X2")
      (value "X321532768KGD2SI")
      (footprint "CR_3215_32768")
      (fields (field (name "NAME") "32.768kHz") (field (name "MANUFACTURER") "YXC(扬兴晶振)"))
      (libsource (lib "altium-import") (part "root_0_X321532768KGD2SI_"))
    )
  )
  (nets
    (net (code "1") (name "/BOOT0") (class "Default")
      (node (ref "R8") (pin "1") (pinfunction "1_1") (pintype "passive"))
      (node (ref "R9") (pin "1") (pinfunction "1_1") (pintype "passive"))
      (node (ref "U2") (pin "138") (pinfunction "BOOT0_138") (pintype "passive"))
    )
    (net (code "2") (name "/FSMC_A0") (class "Default")
      (node (ref "U2") (pin "10") (pinfunction "PF00_10") (pintype "passive"))
      (node (ref "U3") (pin "5") (pinfunction "A4_5") (pintype "passive"))
    )
    (net (code "3") (name "/FSMC_A1") (class "Default")
      (node (ref "U2") (pin "11") (pinfunction "PF01_11") (pintype "passive"))
      (node (ref "U3") (pin "4") (pinfunction "A3_4") (pintype "passive"))
    )
    (net (code "4") (name "/FSMC_A2") (class "Default")
      (node (ref "U2") (pin "12") (pinfunction "PF02_12") (pintype "passive"))
      (node (ref "U3") (pin "3") (pinfunction "A2_3") (pintype "passive"))
    )
    (net (code "5") (name "/FSMC_A3") (class "Default")
      (node (ref "U2") (pin "13") (pinfunction "PF03_13") (pintype "passive"))
      (node (ref "U3") (pin "2") (pinfunction "A1_2") (pintype "passive"))
    )
    (net (code "6") (name "/FSMC_A4") (class "Default")
      (node (ref "U2") (pin "14") (pinfunction "PF04_14") (pintype "passive"))
      (node (ref "U3") (pin "1") (pinfunction "A0_1") (pintype "passive"))
    )
    (net (code "7") (name "/FSMC_A5") (class "Default")
      (node (ref "U2") (pin "15") (pinfunction "PF05_15") (pintype "passive"))
      (node (ref "U3") (pin "18") (pinfunction "A5_18") (pintype "passive"))
    )
    (net (code "8") (name "/FSMC_A6") (class "Default")
      (node (ref "LCM1") (pin "2") (pinfunction "RS_2") (pintype "passive"))
      (node (ref "U2") (pin "50") (pinfunction "PF12_50") (pintype "passive"))
      (node (ref "U3") (pin "19") (pinfunction "A6_19") (pintype "passive"))
    )
    (net (code "9") (name "/FSMC_A7") (class "Default")
      (node (ref "U2") (pin "53") (pinfunction "PF13_53") (pintype "passive"))
      (node (ref "U3") (pin "20") (pinfunction "A7_20") (pintype "passive"))
    )
    (net (code "10") (name "/FSMC_A8") (class "Default")
      (node (ref "U2") (pin "54") (pinfunction "PF14_54") (pintype "passive"))
      (node (ref "U3") (pin "21") (pinfunction "A8_21") (pintype "passive"))
    )
    (net (code "11") (name "/FSMC_A9") (class "Default")
      (node (ref "U2") (pin "55") (pinfunction "PF15_55") (pintype "passive"))
      (node (ref "U3") (pin "22") (pinfunction "A9_22") (pintype "passive"))
    )
    (net (code "12") (name "/FSMC_A10") (class "Default")
      (node (ref "U2") (pin "56") (pinfunction "PG00_56") (pintype "passive"))
      (node (ref "U3") (pin "23") (pinfunction "A10_23") (pintype "passive"))
    )
    (net (code "13") (name "/FSMC_A11") (class "Default")
      (node (ref "U2") (pin "57") (pinfunction "PG01_57") (pintype "passive"))
      (node (ref "U3") (pin "24") (pinfunction "A11_24") (pintype "passive"))
    )
    (net (code "14") (name "/FSMC_A12") (class "Default")
      (node (ref "U2") (pin "87") (pinfunction "PG02_87") (pintype "passive"))
      (node (ref "U3") (pin "42") (pinfunction "A15_42") (pintype "passive"))
    )
    (net (code "15") (name "/FSMC_A13") (class "Default")
      (node (ref "U2") (pin "88") (pinfunction "PG03_88") (pintype "passive"))
      (node (ref "U3") (pin "27") (pinfunction "A14_27") (pintype "passive"))
    )
    (net (code "16") (name "/FSMC_A14") (class "Default")
      (node (ref "U2") (pin "89") (pinfunction "PG04_89") (pintype "passive"))
      (node (ref "U3") (pin "26") (pinfunction "A13_26") (pintype "passive"))
    )
    (net (code "17") (name "/FSMC_A15") (class "Default")
      (node (ref "U2") (pin "90") (pinfunction "PG05_90") (pintype "passive"))
      (node (ref "U3") (pin "25") (pinfunction "A12_25") (pintype "passive"))
    )
    (net (code "18") (name "/FSMC_A16") (class "Default")
      (node (ref "U2") (pin "80") (pinfunction "PD11_80") (pintype "passive"))
      (node (ref "U3") (pin "43") (pinfunction "A16_43") (pintype "passive"))
    )
    (net (code "19") (name "/FSMC_A17") (class "Default")
      (node (ref "U2") (pin "81") (pinfunction "PD12_81") (pintype "passive"))
      (node (ref "U3") (pin "44") (pinfunction "A17_44") (pintype "passive"))
    )
    (net (code "20") (name "/FSMC_A18") (class "Default")
      (node (ref "U2") (pin "82") (pinfunction "PD13_82") (pintype "passive"))
      (node (ref "U3") (pin "28") (pinfunction "A18_28") (pintype "passive"))
    )
    (net (code "21") (name "/FSMC_D0") (class "Default")
      (node (ref "LCM1") (pin "6") (pinfunction "DB0_6") (pintype "passive"))
      (node (ref "U2") (pin "85") (pinfunction "PD14_85") (pintype "passive"))
      (node (ref "U3") (pin "7") (pinfunction "I/O0_7") (pintype "passive"))
    )
    (net (code "22") (name "/FSMC_D1") (class "Default")
      (node (ref "LCM1") (pin "7") (pinfunction "DB1_7") (pintype "passive"))
      (node (ref "U2") (pin "86") (pinfunction "PD15_86") (pintype "passive"))
      (node (ref "U3") (pin "8") (pinfunction "I/O1_8") (pintype "passive"))
    )
    (net (code "23") (name "/FSMC_D2") (class "Default")
      (node (ref "LCM1") (pin "8") (pinfunction "DB2_8") (pintype "passive"))
      (node (ref "U2") (pin "114") (pinfunction "PD00_114") (pintype "passive"))
      (node (ref "U3") (pin "9") (pinfunction "I/O2_9") (pintype "passive"))
    )
    (net (code "24") (name "/FSMC_D3") (class "Default")
      (node (ref "LCM1") (pin "9") (pinfunction "DB3_9") (pintype "passive"))
      (node (ref "U2") (pin "115") (pinfunction "PD01_115") (pintype "passive"))
      (node (ref "U3") (pin "10") (pinfunction "I/O3_10") (pintype "passive"))
    )
    (net (code "25") (name "/FSMC_D4") (class "Default")
      (node (ref "LCM1") (pin "10") (pinfunction "DB4_10") (pintype "passive"))
      (node (ref "U2") (pin "58") (pinfunction "PE07_58") (pintype "passive"))
      (node (ref "U3") (pin "13") (pinfunction "I/O4_13") (pintype "passive"))
    )
    (net (code "26") (name "/FSMC_D5") (class "Default")
      (node (ref "LCM1") (pin "11") (pinfunction "DB5_11") (pintype "passive"))
      (node (ref "U2") (pin "59") (pinfunction "PE08_59") (pintype "passive"))
      (node (ref "U3") (pin "14") (pinfunction "I/O5_14") (pintype "passive"))
    )
    (net (code "27") (name "/FSMC_D6") (class "Default")
      (node (ref "LCM1") (pin "12") (pinfunction "DB6_12") (pintype "passive"))
      (node (ref "U2") (pin "60") (pinfunction "PE09_60") (pintype "passive"))
      (node (ref "U3") (pin "15") (pinfunction "I/O6_15") (pintype "passive"))
    )
    (net (code "28") (name "/FSMC_D7") (class "Default")
      (node (ref "LCM1") (pin "13") (pinfunction "DB7_13") (pintype "passive"))
      (node (ref "U2") (pin "63") (pinfunction "PE10_63") (pintype "passive"))
      (node (ref "U3") (pin "16") (pinfunction "I/O7_16") (pintype "passive"))
    )
    (net (code "29") (name "/FSMC_D8") (class "Default")
      (node (ref "LCM1") (pin "14") (pinfunction "DB8_14") (pintype "passive"))
      (node (ref "U2") (pin "64") (pinfunction "PE11_64") (pintype "passive"))
      (node (ref "U3") (pin "29") (pinfunction "I/O8_29") (pintype "passive"))
    )
    (net (code "30") (name "/FSMC_D9") (class "Default")
      (node (ref "LCM1") (pin "15") (pinfunction "DB9_15") (pintype "passive"))
      (node (ref "U2") (pin "65") (pinfunction "PE12_65") (pintype "passive"))
      (node (ref "U3") (pin "30") (pinfunction "I/O9_30") (pintype "passive"))
    )
    (net (code "31") (name "/FSMC_D10") (class "Default")
      (node (ref "LCM1") (pin "16") (pinfunction "DB10_16") (pintype "passive"))
      (node (ref "U2") (pin "66") (pinfunction "PE13_66") (pintype "passive"))
      (node (ref "U3") (pin "31") (pinfunction "I/O10_31") (pintype "passive"))
    )
    (net (code "32") (name "/FSMC_D11") (class "Default")
      (node (ref "LCM1") (pin "17") (pinfunction "DB11_17") (pintype "passive"))
      (node (ref "U2") (pin "67") (pinfunction "PE14_67") (pintype "passive"))
      (node (ref "U3") (pin "32") (pinfunction "I/O11_32") (pintype "passive"))
    )
    (net (code "33") (name "/FSMC_D12") (class "Default")
      (node (ref "LCM1") (pin "18") (pinfunction "DB12_18") (pintype "passive"))
      (node (ref "U2") (pin "68") (pinfunction "PE15_68") (pintype "passive"))
      (node (ref "U3") (pin "35") (pinfunction "I/O12_35") (pintype "passive"))
    )
    (net (code "34") (name "/FSMC_D13") (class "Default")
      (node (ref "LCM1") (pin "19") (pinfunction "DB13_19") (pintype "passive"))
      (node (ref "U2") (pin "77") (pinfunction "PD08_77") (pintype "passive"))
      (node (ref "U3") (pin "36") (pinfunction "I/O13_36") (pintype "passive"))
    )
    (net (code "35") (name "/FSMC_D14") (class "Default")
      (node (ref "LCM1") (pin "20") (pinfunction "DB14_20") (pintype "passive"))
      (node (ref "U2") (pin "78") (pinfunction "PD09_78") (pintype "passive"))
      (node (ref "U3") (pin "37") (pinfunction "I/O14_37") (pintype "passive"))
    )
    (net (code "36") (name "/FSMC_D15") (class "Default")
      (node (ref "LCM1") (pin "21") (pinfunction "DB15_21") (pintype "passive"))
      (node (ref "U2") (pin "79") (pinfunction "PD10_79") (pintype "passive"))
      (node (ref "U3") (pin "38") (pinfunction "I/O15_38") (pintype "passive"))
    )
    (net (code "37") (name "/FSMC_NBL0") (class "Default")
      (node (ref "U2") (pin "141") (pinfunction "PE00_141") (pintype "passive"))
      (node (ref "U3") (pin "39") (pinfunction "~{BLE}_39") (pintype "passive"))
    )
    (net (code "38") (name "/FSMC_NBL1") (class "Default")
      (node (ref "U2") (pin "142") (pinfunction "PE01_142") (pintype "passive"))
      (node (ref "U3") (pin "40") (pinfunction "~{BHE}_40") (pintype "passive"))
    )
    (net (code "39") (name "/FSMC_NE1") (class "Default")
      (node (ref "R3") (pin "1") (pinfunction "1_1") (pintype "passive"))
      (node (ref "U2") (pin "123") (pinfunction "PD07_123") (pintype "passive"))
      (node (ref "U3") (pin "6") (pinfunction "~{CE}_6") (pintype "passive"))
    )
    (net (code "40") (name "/FSMC_NE4") (class "Default")
      (node (ref "LCM1") (pin "1") (pinfunction "~{CS}_1") (pintype "passive"))
      (node (ref "U2") (pin "127") (pinfunction "PG12_127") (pintype "passive"))
    )
    (net (code "41") (name "/FSMC_NOE") (class "Default")
      (node (ref "LCM1") (pin "4") (pinfunction "~{RD}_4") (pintype "passive"))
      (node (ref "U2") (pin "118") (pinfunction "PD04_118") (pintype "passive"))
      (node (ref "U3") (pin "41") (pinfunction "~{OE}_41") (pintype "passive"))
    )
    (net (code "42") (name "/FSMC_NWE") (class "Default")
      (node (ref "LCM1") (pin "3") (pinfunction "~{WR}_3") (pintype "passive"))
      (node (ref "U2") (pin "119") (pinfunction "PD05_119") (pintype "passive"))
      (node (ref "U3") (pin "17") (pinfunction "~{WE}_17") (pintype "passive"))
    )
    (net (code "43") (name "/PA2_USART2_TX") (class "Default")
      (node (ref "R32") (pin "2") (pinfunction "2_2") (pintype "passive"))
      (node (ref "R46") (pin "2") (pinfunction "2_2") (pintype "passive"))
      (node (ref "U2") (pin "36") (pinfunction "PA02_36") (pintype "passive"))
    )
    (net (code "44") (name "/PA3_USART2_RX") (class "Default")
      (node (ref "R28") (pin "2") (pinfunction "2_2") (pintype "passive"))
      (node (ref "R43") (pin "2") (pinfunction "2_2") (pintype "passive"))
      (node (ref "U2") (pin "37") (pinfunction "PA03_37") (pintype "passive"))
    )
    (net (code "45") (name "/PA4_USART2_CK") (class "Default")
      (node (ref "R37") (pin "2") (pinfunction "2_2") (pintype "passive"))
      (node (ref "R49") (pin "2") (pinfunction "2_2") (pintype "passive"))
      (node (ref "U2") (pin "40") (pinfunction "PA04_40") (pintype "passive"))
    )
    (net (code "46") (name "/PA5_SPI1_SCK") (class "Default")
      (node (ref "R26") (pin "2") (pinfunction "2_2") (pintype "passive"))
      (node (ref "U2") (pin "41") (pinfunction "PA05_41") (pintype "passive"))
    )
    (net (code "47") (name "/PA6_SPI1_MISO") (class "Default")
      (node (ref "R30") (pin "2") (pinfunction "2_2") (pintype "passive"))
      (node (ref "U2") (pin "42") (pinfunction "PA06_42") (pintype "passive"))
    )
    (net (code "48") (name "/PA7_SPI1_MOSI") (class "Default")
      (node (ref "R35") (pin "2") (pinfunction "2_2") (pintype "passive"))
      (node (ref "U2") (pin "43") (pinfunction "PA07_43") (pintype "passive"))
    )
    (net (code "49") (name "/PA8_USART1_CX") (class "Default")
      (node (ref "R36") (pin "2") (pinfunction "2_2") (pintype "passive"))
      (node (ref "R41") (pin "2") (pinfunction "2_2") (pintype "passive"))
      (node (ref "U2") (pin "100") (pinfunction "PA08_100") (pintype "passive"))
    )
    (net (code "50") (name "/PA9_USART1_TX") (class "Default")
      (node (ref "R31") (pin "2") (pinfunction "2_2") (pintype "passive"))
      (node (ref "R40") (pin "2") (pinfunction "2_2") (pintype "passive"))
      (node (ref "U2") (pin "101") (pinfunction "PA09_101") (pintype "passive"))
    )
    (net (code "51") (name "/PA10_USART1_RX") (class "Default")
      (node (ref "R27") (pin "2") (pinfunction "2_2") (pintype "passive"))
      (node (ref "R39") (pin "2") (pinfunction "2_2") (pintype "passive"))
      (node (ref "U2") (pin "102") (pinfunction "PA10_102") (pintype "passive"))
    )
    (net (code "52") (name "/PA11_CAN1_RX") (class "Default")
      (node (ref "U2") (pin "103") (pinfunction "PA11_103") (pintype "passive"))
    )
    (net (code "53") (name "/PA12_CAN1_TX") (class "Default")
      (node (ref "U2") (pin "104") (pinfunction "PA12_104") (pintype "passive"))
    )
    (net (code "54") (name "/PA15_SPI1_NSS") (class "Default")
      (node (ref "R38") (pin "2") (pinfunction "2_2") (pintype "passive"))
      (node (ref "U2") (pin "110") (pinfunction "PA15_110") (pintype "passive"))
    )
    (net (code "55") (name "/PB4_TIM3_CH1") (class "Default")
      (node (ref "C29") (pin "1") (pinfunction "1_1") (pintype "passive"))
      (node (ref "R61") (pin "1") (pinfunction "1_1") (pintype "passive"))
      (node (ref "SW7") (pin "B") (pinfunction "B_B") (pintype "passive"))
      (node (ref "U2") (pin "134") (pinfunction "PB04_134") (pintype "passive"))
    )
    (net (code "56") (name "/PB5_TIM3_CH2") (class "Default")
      (node (ref "C28") (pin "1") (pinfunction "1_1") (pintype "passive"))
      (node (ref "R52") (pin "1") (pinfunction "1_1") (pintype "passive"))
      (node (ref "SW7") (pin "A") (pinfunction "A_A") (pintype "passive"))
      (node (ref "U2") (pin "135") (pinfunction "PB05_135") (pintype "passive"))
    )
    (net (code "57") (name "/PB6_TIM4_CH1") (class "Default")
      (node (ref "C25") (pin "1") (pinfunction "1_1") (pintype "passive"))
      (node (ref "R60") (pin "1") (pinfunction "1_1") (pintype "passive"))
      (node (ref "SW6") (pin "B") (pinfunction "B_B") (pintype "passive"))
      (node (ref "U2") (pin "136") (pinfunction "PB06_136") (pintype "passive"))
    )
    (net (code "58") (name "/PB7_TIM4_CH2") (class "Default")
      (node (ref "C24") (pin "1") (pinfunction "1_1") (pintype "passive"))
      (node (ref "R59") (pin "1") (pinfunction "1_1") (pintype "passive"))
      (node (ref "SW6") (pin "A") (pinfunction "A_A") (pintype "passive"))
      (node (ref "U2") (pin "137") (pinfunction "PB07_137") (pintype "passive"))
    )
    (net (code "59") (name "/PB8_I2C1_SCL") (class "Default")
      (node (ref "R51") (pin "2") (pinfunction "2_2") (pintype "passive"))
      (node (ref "R54") (pin "2") (pinfunction "2_2") (pintype "passive"))
      (node (ref "U2") (pin "139") (pinfunction "PB08_139") (pintype "passive"))
    )
    (net (code "60") (name "/PB9_I2C1_SDA") (class "Default")
      (node (ref "R53") (pin "2") (pinfunction "2_2") (pintype "passive"))
      (node (ref "R55") (pin "2") (pinfunction "2_2") (pintype "passive"))
      (node (ref "U2") (pin "140") (pinfunction "PB09_140") (pintype "passive"))
    )
    (net (code "61") (name "/PB10_USART3_TX") (class "Default")
      (node (ref "U2") (pin "69") (pinfunction "PB10_69") (pintype "passive"))
    )
    (net (code "62") (name "/PB11_USART3_RX") (class "Default")
      (node (ref "U2") (pin "70") (pinfunction "PB11_70") (pintype "passive"))
    )
    (net (code "63") (name "/PB12_SPI2_NSS") (class "Default")
      (node (ref "U2") (pin "73") (pinfunction "PB12_73") (pintype "passive"))
    )
    (net (code "64") (name "/PB13_SPI2_SCK") (class "Default")
      (node (ref "U2") (pin "74") (pinfunction "PB13_74") (pintype "passive"))
    )
    (net (code "65") (name "/PB15_LCD_BLK") (class "Default")
      (node (ref "LCM1") (pin "23") (pinfunction "BL_23") (pintype "passive"))
      (node (ref "U2") (pin "76") (pinfunction "PB15_76") (pintype "passive"))
    )
    (net (code "66") (name "/PC2_SPI2_MISO") (class "Default")
      (node (ref "U2") (pin "28") (pinfunction "PC02_28") (pintype "passive"))
    )
    (net (code "67") (name "/PC3_SPI2_MOSI") (class "Default")
      (node (ref "U2") (pin "29") (pinfunction "PC03_29") (pintype "passive"))
    )
    (net (code "68") (name "/PC4_KEY0") (class "Default")
      (node (ref "C52") (pin "1") (pinfunction "1_1") (pintype "passive"))
      (node (ref "R44") (pin "1") (pinfunction "1_1") (pintype "passive"))
      (node (ref "SW6") (pin "D") (pinfunction "D_D") (pintype "passive"))
      (node (ref "U2") (pin "44") (pinfunction "PC04_44") (pintype "passive"))
    )
    (net (code "69") (name "/PC5_KEY1") (class "Default")
      (node (ref "C27") (pin "1") (pinfunction "1_1") (pintype "passive"))
      (node (ref "R24") (pin "1") (pinfunction "1_1") (pintype "passive"))
      (node (ref "SW7") (pin "D") (pinfunction "D_D") (pintype "passive"))
      (node (ref "U2") (pin "45") (pinfunction "PC05_45") (pintype "passive"))
    )
    (net (code "70") (name "/PC6_USART6_TX") (class "Default")
      (node (ref "U2") (pin "96") (pinfunction "PC06_96") (pintype "passive"))
    )
    (net (code "71") (name "/PC7_USART6_RX") (class "Default")
      (node (ref "U2") (pin "97") (pinfunction "PC07_97") (pintype "passive"))
    )
    (net (code "72") (name "/PC8_485_CTR") (class "Default")
      (node (ref "U2") (pin "98") (pinfunction "PC08_98") (pintype "passive"))
    )
    (net (code "73") (name "/PE2_KEY2") (class "Default")
      (node (ref "C41") (pin "1") (pinfunction "1_1") (pintype "passive"))
      (node (ref "R23") (pin "2") (pinfunction "2_2") (pintype "passive"))
      (node (ref "SW2") (pin "3") (pinfunction "3_3") (pintype "passive"))
      (node (ref "SW2") (pin "4") (pinfunction "4_4") (pintype "passive"))
      (node (ref "U2") (pin "1") (pinfunction "PE02_1") (pintype "passive"))
    )
    (net (code "74") (name "/PE3_KEY3") (class "Default")
      (node (ref "C48") (pin "1") (pinfunction "1_1") (pintype "passive"))
      (node (ref "R33") (pin "2") (pinfunction "2_2") (pintype "passive"))
      (node (ref "SW3") (pin "3") (pinfunction "3_3") (pintype "passive"))
      (node (ref "SW3") (pin "4") (pinfunction "4_4") (pintype "passive"))
      (node (ref "U2") (pin "2") (pinfunction "PE03_2") (pintype "passive"))
    )
    (net (code "75") (name "/PE4_KEY4") (class "Default")
      (node (ref "C49") (pin "1") (pinfunction "1_1") (pintype "passive"))
      (node (ref "R34") (pin "2") (pinfunction "2_2") (pintype "passive"))
      (node (ref "SW4") (pin "3") (pinfunction "3_3") (pintype "passive"))
      (node (ref "SW4") (pin "4") (pinfunction "4_4") (pintype "passive"))
      (node (ref "U2") (pin "3") (pinfunction "PE04_3") (pintype "passive"))
    )
    (net (code "76") (name "/PE5_KEY5") (class "Default")
      (node (ref "C47") (pin "1") (pinfunction "1_1") (pintype "passive"))
      (node (ref "R29") (pin "2") (pinfunction "2_2") (pintype "passive"))
      (node (ref "SW5") (pin "3") (pinfunction "3_3") (pintype "passive"))
      (node (ref "SW5") (pin "4") (pinfunction "4_4") (pintype "passive"))
      (node (ref "U2") (pin "4") (pinfunction "PE05_4") (pintype "passive"))
    )
    (net (code "77") (name "/PE6_KEY6") (class "Default")
      (node (ref "C43") (pin "1") (pinfunction "1_1") (pintype "passive"))
      (node (ref "R25") (pin "2") (pinfunction "2_2") (pintype "passive"))
      (node (ref "SW1") (pin "3") (pinfunction "3_3") (pintype "passive"))
      (node (ref "SW1") (pin "4") (pinfunction "4_4") (pintype "passive"))
      (node (ref "U2") (pin "5") (pinfunction "PE06_5") (pintype "passive"))
    )
    (net (code "78") (name "/PF6_LED0") (class "Default")
      (node (ref "LED2") (pin "1") (pinfunction "K_1") (pintype "passive"))
      (node (ref "U2") (pin "18") (pinfunction "PF06_18") (pintype "passive"))
    )
    (net (code "79") (name "/PF7_LED1") (class "Default")
      (node (ref "LED3") (pin "1") (pinfunction "K_1") (pintype "passive"))
      (node (ref "U2") (pin "19") (pinfunction "PF07_19") (pintype "passive"))
    )
    (net (code "80") (name "/PF8_LED2") (class "Default")
      (node (ref "LED4") (pin "1") (pinfunction "K_1") (pintype "passive"))
      (node (ref "U2") (pin "20") (pinfunction "PF08_20") (pintype "passive"))
    )
    (net (code "81") (name "/PF9_LED3") (class "Default")
      (node (ref "LED5") (pin "1") (pinfunction "K_1") (pintype "passive"))
      (node (ref "U2") (pin "21") (pinfunction "PF09_21") (pintype "passive"))
    )
    (net (code "82") (name "/RESET") (class "Default")
      (node (ref "C12") (pin "2") (pinfunction "2_2") (pintype "passive"))
      (node (ref "LCM1") (pin "5") (pinfunction "~{RESET}_5") (pintype "passive"))
      (node (ref "R10") (pin "2") (pinfunction "2_2") (pintype "passive"))
      (node (ref "U2") (pin "25") (pinfunction "nRESET_25") (pintype "passive"))
    )
    (net (code "83") (name "/SWCLK") (class "Default")
      (node (ref "R20") (pin "1") (pinfunction "1_1") (pintype "passive"))
      (node (ref "U2") (pin "109") (pinfunction "PA14_109") (pintype "passive"))
    )
    (net (code "84") (name "/SWDIO") (class "Default")
      (node (ref "R19") (pin "1") (pinfunction "1_1") (pintype "passive"))
      (node (ref "U2") (pin "105") (pinfunction "PA13_105") (pintype "passive"))
    )
    (net (code "85") (name "/SWO") (class "Default")
      (node (ref "R21") (pin "1") (pinfunction "1_1") (pintype "passive"))
      (node (ref "U2") (pin "133") (pinfunction "PB03_133") (pintype "passive"))
    )
    (net (code "86") (name "3V3") (class "Default")
      (node (ref "C1") (pin "2") (pinfunction "2_2") (pintype "passive"))
      (node (ref "C13") (pin "2") (pinfunction "2_2") (pintype "passive"))
      (node (ref "C14") (pin "2") (pinfunction "2_2") (pintype "passive"))
      (node (ref "C18") (pin "2") (pinfunction "2_2") (pintype "passive"))
      (node (ref "C19") (pin "2") (pinfunction "2_2") (pintype "passive"))
      (node (ref "C2") (pin "2") (pinfunction "2_2") (pintype "passive"))
      (node (ref "C20") (pin "2") (pinfunction "2_2") (pintype "passive"))
      (node (ref "C21") (pin "2") (pinfunction "2_2") (pintype "passive"))
      (node (ref "C22") (pin "2") (pinfunction "2_2") (pintype "passive"))
      (node (ref "CN3") (pin "1") (pinfunction "1_1") (pintype "passive"))
      (node (ref "D1") (pin "2") (pinfunction "A_2") (pintype "passive"))
      (node (ref "L1") (pin "1") (pinfunction "1_1") (pintype "passive"))
      (node (ref "LCM1") (pin "24") (pinfunction "VDD_24") (pintype "passive"))
      (node (ref "R10") (pin "1") (pinfunction "1_1") (pintype "passive"))
      (node (ref "R23") (pin "1") (pinfunction "1_1") (pintype "passive"))
      (node (ref "R24") (pin "2") (pinfunction "2_2") (pintype "passive"))
      (node (ref "R25") (pin "1") (pinfunction "1_1") (pintype "passive"))
      (node (ref "R29") (pin "1") (pinfunction "1_1") (pintype "passive"))
      (node (ref "R3") (pin "2") (pinfunction "2_2") (pintype "passive"))
      (node (ref "R33") (pin "1") (pinfunction "1_1") (pintype "passive"))
      (node (ref "R34") (pin "1") (pinfunction "1_1") (pintype "passive"))
      (node (ref "R39") (pin "1") (pinfunction "1_1") (pintype "passive"))
      (node (ref "R40") (pin "1") (pinfunction "1_1") (pintype "passive"))
      (node (ref "R41") (pin "1") (pinfunction "1_1") (pintype "passive"))
      (node (ref "R42") (pin "1") (pinfunction "1_1") (pintype "passive"))
      (node (ref "R43") (pin "1") (pinfunction "1_1") (pintype "passive"))
      (node (ref "R44") (pin "2") (pinfunction "2_2") (pintype "passive"))
      (node (ref "R45") (pin "1") (pinfunction "1_1") (pintype "passive"))
      (node (ref "R46") (pin "1") (pinfunction "1_1") (pintype "passive"))
      (node (ref "R47") (pin "1") (pinfunction "1_1") (pintype "passive"))
      (node (ref "R48") (pin "1") (pinfunction "1_1") (pintype "passive"))
      (node (ref "R49") (pin "1") (pinfunction "1_1") (pintype "passive"))
      (node (ref "R52") (pin "2") (pinfunction "2_2") (pintype "passive"))
      (node (ref "R54") (pin "1") (pinfunction "1_1") (pintype "passive"))
      (node (ref "R55") (pin "1") (pinfunction "1_1") (pintype "passive"))
      (node (ref "R59") (pin "2") (pinfunction "2_2") (pintype "passive"))
      (node (ref "R60") (pin "2") (pinfunction "2_2") (pintype "passive"))
      (node (ref "R61") (pin "2") (pinfunction "2_2") (pintype "passive"))
      (node (ref "R8") (pin "2") (pinfunction "2_2") (pintype "passive"))
      (node (ref "U12") (pin "1") (pinfunction "1_1") (pintype "passive"))
      (node (ref "U13") (pin "1") (pinfunction "1_1") (pintype "passive"))
      (node (ref "U14") (pin "1") (pinfunction "1_1") (pintype "passive"))
      (node (ref "U19") (pin "1") (pinfunction "1_1") (pintype "passive"))
      (node (ref "U2") (pin "108") (pinfunction "VDD_108") (pintype "passive"))
      (node (ref "U2") (pin "121") (pinfunction "VDD_121") (pintype "passive"))
      (node (ref "U2") (pin "131") (pinfunction "VDD_131") (pintype "passive"))
      (node (ref "U2") (pin "143") (pinfunction "PDR_ON_143") (pintype "passive"))
      (node (ref "U2") (pin "144") (pinfunction "VDD_144") (pintype "passive"))
      (node (ref "U2") (pin "17") (pinfunction "VDD_17") (pintype "passive"))
      (node (ref "U2") (pin "30") (pinfunction "VDD_30") (pintype "passive"))
      (node (ref "U2") (pin "39") (pinfunction "VDD_39") (pintype "passive"))
      (node (ref "U2") (pin "52") (pinfunction "VDD_52") (pintype "passive"))
      (node (ref "U2") (pin "62") (pinfunction "VDD_62") (pintype "passive"))
      (node (ref "U2") (pin "72") (pinfunction "VDD_72") (pintype "passive"))
      (node (ref "U2") (pin "84") (pinfunction "VDD_84") (pintype "passive"))
      (node (ref "U2") (pin "95") (pinfunction "VDD_95") (pintype "passive"))
      (node (ref "U3") (pin "11") (pinfunction "VDD_11") (pintype "passive"))
      (node (ref "U3") (pin "33") (pinfunction "VDD_33") (pintype "passive"))
    )
    (net (code "87") (name "5V") (class "Default")
      (node (ref "U15") (pin "1") (pinfunction "1_1") (pintype "passive"))
      (node (ref "U16") (pin "1") (pinfunction "1_1") (pintype "passive"))
      (node (ref "U17") (pin "1") (pinfunction "1_1") (pintype "passive"))
      (node (ref "U21") (pin "1") (pinfunction "1_1") (pintype "passive"))
    )
    (net (code "88") (name "A3V3") (class "Default")
      (node (ref "C15") (pin "2") (pinfunction "2_2") (pintype "passive"))
      (node (ref "L1") (pin "2") (pinfunction "2_2") (pintype "passive"))
      (node (ref "L2") (pin "1") (pinfunction "1_1") (pintype "passive"))
      (node (ref "U2") (pin "33") (pinfunction "VDDA_33") (pintype "passive"))
    )
    (net (code "89") (name "AGND") (class "Default")
      (node (ref "BT1") (pin "2") (pinfunction "2_2") (pintype "passive"))
      (node (ref "C1") (pin "1") (pinfunction "1_1") (pintype "passive"))
      (node (ref "C10") (pin "1") (pinfunction "1_1") (pintype "passive"))
      (node (ref "C11") (pin "1") (pinfunction "1_1") (pintype "passive"))
      (node (ref "C12") (pin "1") (pinfunction "1_1") (pintype "passive"))
      (node (ref "C13") (pin "1") (pinfunction "1_1") (pintype "passive"))
      (node (ref "C14") (pin "1") (pinfunction "1_1") (pintype "passive"))
      (node (ref "C15") (pin "1") (pinfunction "1_1") (pintype "passive"))
      (node (ref "C16") (pin "1") (pinfunction "1_1") (pintype "passive"))
      (node (ref "C18") (pin "1") (pinfunction "1_1") (pintype "passive"))
      (node (ref "C19") (pin "1") (pinfunction "1_1") (pintype "passive"))
      (node (ref "C2") (pin "1") (pinfunction "1_1") (pintype "passive"))
      (node (ref "C20") (pin "1") (pinfunction "1_1") (pintype "passive"))
      (node (ref "C21") (pin "1") (pinfunction "1_1") (pintype "passive"))
      (node (ref "C22") (pin "1") (pinfunction "1_1") (pintype "passive"))
      (node (ref "C24") (pin "2") (pinfunction "2_2") (pintype "passive"))
      (node (ref "C25") (pin "2") (pinfunction "2_2") (pintype "passive"))
      (node (ref "C27") (pin "2") (pinfunction "2_2") (pintype "passive"))
      (node (ref "C28") (pin "2") (pinfunction "2_2") (pintype "passive"))
      (node (ref "C29") (pin "2") (pinfunction "2_2") (pintype "passive"))
      (node (ref "C41") (pin "2") (pinfunction "2_2") (pintype "passive"))
      (node (ref "C43") (pin "2") (pinfunction "2_2") (pintype "passive"))
      (node (ref "C44") (pin "1") (pinfunction "1_1") (pintype "passive"))
      (node (ref "C45") (pin "1") (pinfunction "1_1") (pintype "passive"))
      (node (ref "C46") (pin "1") (pinfunction "1_1") (pintype "passive"))
      (node (ref "C47") (pin "2") (pinfunction "2_2") (pintype "passive"))
      (node (ref "C48") (pin "2") (pinfunction "2_2") (pintype "passive"))
      (node (ref "C49") (pin "2") (pinfunction "2_2") (pintype "passive"))
      (node (ref "C50") (pin "1") (pinfunction "1_1") (pintype "passive"))
      (node (ref "C52") (pin "2") (pinfunction "2_2") (pintype "passive"))
      (node (ref "C6") (pin "2") (pinfunction "2_2") (pintype "passive"))
      (node (ref "C7") (pin "2") (pinfunction "2_2") (pintype "passive"))
      (node (ref "C8") (pin "1") (pinfunction "1_1") (pintype "passive"))
      (node (ref "C9") (pin "1") (pinfunction "1_1") (pintype "passive"))
      (node (ref "CN3") (pin "6") (pinfunction "6_6") (pintype "passive"))
      (node (ref "CN4") (pin "2") (pinfunction "2_2") (pintype "passive"))
      (node (ref "CN5") (pin "2") (pinfunction "2_2") (pintype "passive"))
      (node (ref "CN6") (pin "2") (pinfunction "2_2") (pintype "passive"))
      (node (ref "CN8") (pin "2") (pinfunction "2_2") (pintype "passive"))
      (node (ref "D10") (pin "1") (pinfunction "A_1") (pintype "passive"))
      (node (ref "D11") (pin "1") (pinfunction "A_1") (pintype "passive"))
      (node (ref "D12") (pin "1") (pinfunction "A_1") (pintype "passive"))
      (node (ref "D13") (pin "1") (pinfunction "A_1") (pintype "passive"))
      (node (ref "D14") (pin "1") (pinfunction "A_1") (pintype "passive"))
      (node (ref "D15") (pin "1") (pinfunction "A_1") (pintype "passive"))
      (node (ref "D16") (pin "1") (pinfunction "A_1") (pintype "passive"))
      (node (ref "D17") (pin "1") (pinfunction "A_1") (pintype "passive"))
      (node (ref "D18") (pin "1") (pinfunction "A_1") (pintype "passive"))
      (node (ref "D19") (pin "1") (pinfunction "A_1") (pintype "passive"))
      (node (ref "D21") (pin "2") (pinfunction "K_2") (pintype "passive"))
      (node (ref "D24") (pin "1") (pinfunction "A_1") (pintype "passive"))
      (node (ref "D25") (pin "1") (pinfunction "A_1") (pintype "passive"))
      (node (ref "D26") (pin "1") (pinfunction "A_1") (pintype "passive"))
      (node (ref "D27") (pin "1") (pinfunction "A_1") (pintype "passive"))
      (node (ref "D28") (pin "1") (pinfunction "A_1") (pintype "passive"))
      (node (ref "D6") (pin "2") (pinfunction "K_2") (pintype "passive"))
      (node (ref "D8") (pin "2") (pinfunction "K_2") (pintype "passive"))
      (node (ref "D9") (pin "2") (pinfunction "K_2") (pintype "passive"))
      (node (ref "LCM1") (pin "22") (pinfunction "GND_22") (pintype "passive"))
      (node (ref "R9") (pin "2") (pinfunction "2_2") (pintype "passive"))
      (node (ref "SW1") (pin "1") (pinfunction "1_1") (pintype "passive"))
      (node (ref "SW1") (pin "2") (pinfunction "2_2") (pintype "passive"))
      (node (ref "SW2") (pin "1") (pinfunction "1_1") (pintype "passive"))
      (node (ref "SW2") (pin "2") (pinfunction "2_2") (pintype "passive"))
      (node (ref "SW3") (pin "1") (pinfunction "1_1") (pintype "passive"))
      (node (ref "SW3") (pin "2") (pinfunction "2_2") (pintype "passive"))
      (node (ref "SW4") (pin "1") (pinfunction "1_1") (pintype "passive"))
      (node (ref "SW4") (pin "2") (pinfunction "2_2") (pintype "passive"))
      (node (ref "SW5") (pin "1") (pinfunction "1_1") (pintype "passive"))
      (node (ref "SW5") (pin "2") (pinfunction "2_2") (pintype "passive"))
      (node (ref "SW6") (pin "C") (pinfunction "C_C") (pintype "passive"))
      (node (ref "SW6") (pin "E") (pinfunction "E_E") (pintype "passive"))
      (node (ref "SW6") (pin "MH1") (pinfunction "MH1_MH1") (pintype "passive"))
      (node (ref "SW6") (pin "MH2") (pinfunction "MH2_MH2") (pintype "passive"))
      (node (ref "SW7") (pin "C") (pinfunction "C_C") (pintype "passive"))
      (node (ref "SW7") (pin "E") (pinfunction "E_E") (pintype "passive"))
      (node (ref "SW7") (pin "MH1") (pinfunction "MH1_MH1") (pintype "passive"))
      (node (ref "SW7") (pin "MH2") (pinfunction "MH2_MH2") (pintype "passive"))
      (node (ref "U2") (pin "107") (pinfunction "VSS_107") (pintype "passive"))
      (node (ref "U2") (pin "120") (pinfunction "VSS_120") (pintype "passive"))
      (node (ref "U2") (pin "130") (pinfunction "VSS_130") (pintype "passive"))
      (node (ref "U2") (pin "16") (pinfunction "VSS_16") (pintype "passive"))
      (node (ref "U2") (pin "31") (pinfunction "VSSA_31") (pintype "passive"))
      (node (ref "U2") (pin "38") (pinfunction "VSS_38") (pintype "passive"))
      (node (ref "U2") (pin "51") (pinfunction "VSS_51") (pintype "passive"))
      (node (ref "U2") (pin "61") (pinfunction "VSS_61") (pintype "passive"))
      (node (ref "U2") (pin "83") (pinfunction "VSS_83") (pintype "passive"))
      (node (ref "U2") (pin "94") (pinfunction "VSS_94") (pintype "passive"))
      (node (ref "U3") (pin "12") (pinfunction "VSS_12") (pintype "passive"))
      (node (ref "U3") (pin "34") (pinfunction "VSS_34") (pintype "passive"))
      (node (ref "X1") (pin "2") (pinfunction "GND_2") (pintype "passive"))
      (node (ref "X1") (pin "4") (pinfunction "GND_4") (pintype "passive"))
    )
    (net (code "90") (name "Net-(D1-K)") (class "Default")
      (node (ref "D1") (pin "1") (pinfunction "K_1") (pintype "passive"))
      (node (ref "D2") (pin "1") (pinfunction "K_1") (pintype "passive"))
      (node (ref "U2") (pin "6") (pinfunction "Vbat_6") (pintype "passive"))
    )
    (net (code "91") (name "Net-(D2-A)") (class "Default")
      (node (ref "BT1") (pin "1") (pinfunction "1_1") (pintype "passive"))
      (node (ref "D2") (pin "2") (pinfunction "A_2") (pintype "passive"))
    )
    (net (code "92") (name "Net-(D6-A)") (class "Default")
      (node (ref "C46") (pin "2") (pinfunction "2_2") (pintype "passive"))
      (node (ref "CN5") (pin "1") (pinfunction "1_1") (pintype "passive"))
      (node (ref "D6") (pin "1") (pinfunction "A_1") (pintype "passive"))
      (node (ref "U12") (pin "2") (pinfunction "2_2") (pintype "passive"))
      (node (ref "U15") (pin "2") (pinfunction "2_2") (pintype "passive"))
    )
    (net (code "93") (name "Net-(D8-A)") (class "Default")
      (node (ref "C44") (pin "2") (pinfunction "2_2") (pintype "passive"))
      (node (ref "CN4") (pin "1") (pinfunction "1_1") (pintype "passive"))
      (node (ref "D8") (pin "1") (pinfunction "A_1") (pintype "passive"))
      (node (ref "U13") (pin "2") (pinfunction "2_2") (pintype "passive"))
      (node (ref "U16") (pin "2") (pinfunction "2_2") (pintype "passive"))
    )
    (net (code "94") (name "Net-(D9-A)") (class "Default")
      (node (ref "C45") (pin "2") (pinfunction "2_2") (pintype "passive"))
      (node (ref "CN6") (pin "1") (pinfunction "1_1") (pintype "passive"))
      (node (ref "D9") (pin "1") (pinfunction "A_1") (pintype "passive"))
      (node (ref "U14") (pin "2") (pinfunction "2_2") (pintype "passive"))
      (node (ref "U17") (pin "2") (pinfunction "2_2") (pintype "passive"))
    )
    (net (code "95") (name "Net-(D10-K)") (class "Default")
      (node (ref "CN4") (pin "3") (pinfunction "3_3") (pintype "passive"))
      (node (ref "D10") (pin "2") (pinfunction "K_2") (pintype "passive"))
      (node (ref "R27") (pin "1") (pinfunction "1_1") (pintype "passive"))
    )
    (net (code "96") (name "Net-(D11-K)") (class "Default")
      (node (ref "CN4") (pin "4") (pinfunction "4_4") (pintype "passive"))
      (node (ref "D11") (pin "2") (pinfunction "K_2") (pintype "passive"))
      (node (ref "R31") (pin "1") (pinfunction "1_1") (pintype "passive"))
    )
    (net (code "97") (name "Net-(D12-K)") (class "Default")
      (node (ref "CN4") (pin "5") (pinfunction "5_5") (pintype "passive"))
      (node (ref "D12") (pin "2") (pinfunction "K_2") (pintype "passive"))
      (node (ref "R36") (pin "1") (pinfunction "1_1") (pintype "passive"))
    )
    (net (code "98") (name "Net-(D13-K)") (class "Default")
      (node (ref "CN6") (pin "3") (pinfunction "3_3") (pintype "passive"))
      (node (ref "D13") (pin "2") (pinfunction "K_2") (pintype "passive"))
      (node (ref "R28") (pin "1") (pinfunction "1_1") (pintype "passive"))
    )
    (net (code "99") (name "Net-(D14-K)") (class "Default")
      (node (ref "CN6") (pin "4") (pinfunction "4_4") (pintype "passive"))
      (node (ref "D14") (pin "2") (pinfunction "K_2") (pintype "passive"))
      (node (ref "R32") (pin "1") (pinfunction "1_1") (pintype "passive"))
    )
    (net (code "100") (name "Net-(D15-K)") (class "Default")
      (node (ref "CN6") (pin "5") (pinfunction "5_5") (pintype "passive"))
      (node (ref "D15") (pin "2") (pinfunction "K_2") (pintype "passive"))
      (node (ref "R37") (pin "1") (pinfunction "1_1") (pintype "passive"))
    )
    (net (code "101") (name "Net-(D16-K)") (class "Default")
      (node (ref "CN5") (pin "6") (pinfunction "6_6") (pintype "passive"))
      (node (ref "D16") (pin "2") (pinfunction "K_2") (pintype "passive"))
      (node (ref "R38") (pin "1") (pinfunction "1_1") (pintype "passive"))
    )
    (net (code "102") (name "Net-(D17-K)") (class "Default")
      (node (ref "CN5") (pin "5") (pinfunction "5_5") (pintype "passive"))
      (node (ref "D17") (pin "2") (pinfunction "K_2") (pintype "passive"))
      (node (ref "R35") (pin "1") (pinfunction "1_1") (pintype "passive"))
    )
    (net (code "103") (name "Net-(D18-K)") (class "Default")
      (node (ref "CN5") (pin "4") (pinfunction "4_4") (pintype "passive"))
      (node (ref "D18") (pin "2") (pinfunction "K_2") (pintype "passive"))
      (node (ref "R30") (pin "1") (pinfunction "1_1") (pintype "passive"))
    )
    (net (code "104") (name "Net-(D19-K)") (class "Default")
      (node (ref "CN5") (pin "3") (pinfunction "3_3") (pintype "passive"))
      (node (ref "D19") (pin "2") (pinfunction "K_2") (pintype "passive"))
      (node (ref "R26") (pin "1") (pinfunction "1_1") (pintype "passive"))
    )
    (net (code "105") (name "Net-(D21-A)") (class "Default")
      (node (ref "C50") (pin "2") (pinfunction "2_2") (pintype "passive"))
      (node (ref "CN8") (pin "1") (pinfunction "1_1") (pintype "passive"))
      (node (ref "D21") (pin "1") (pinfunction "A_1") (pintype "passive"))
      (node (ref "U19") (pin "2") (pinfunction "2_2") (pintype "passive"))
      (node (ref "U21") (pin "2") (pinfunction "2_2") (pintype "passive"))
    )
    (net (code "106") (name "Net-(D24-K)") (class "Default")
      (node (ref "CN8") (pin "3") (pinfunction "3_3") (pintype "passive"))
      (node (ref "D24") (pin "2") (pinfunction "K_2") (pintype "passive"))
      (node (ref "R51") (pin "1") (pinfunction "1_1") (pintype "passive"))
    )
    (net (code "107") (name "Net-(D25-K)") (class "Default")
      (node (ref "CN8") (pin "4") (pinfunction "4_4") (pintype "passive"))
      (node (ref "D25") (pin "2") (pinfunction "K_2") (pintype "passive"))
      (node (ref "R53") (pin "1") (pinfunction "1_1") (pintype "passive"))
    )
    (net (code "108") (name "Net-(D26-K)") (class "Default")
      (node (ref "CN3") (pin "5") (pinfunction "5_5") (pintype "passive"))
      (node (ref "D26") (pin "2") (pinfunction "K_2") (pintype "passive"))
      (node (ref "R19") (pin "2") (pinfunction "2_2") (pintype "passive"))
    )
    (net (code "109") (name "Net-(D27-K)") (class "Default")
      (node (ref "CN3") (pin "4") (pinfunction "4_4") (pintype "passive"))
      (node (ref "D27") (pin "2") (pinfunction "K_2") (pintype "passive"))
      (node (ref "R20") (pin "2") (pinfunction "2_2") (pintype "passive"))
    )
    (net (code "110") (name "Net-(D28-K)") (class "Default")
      (node (ref "CN3") (pin "3") (pinfunction "3_3") (pintype "passive"))
      (node (ref "D28") (pin "2") (pinfunction "K_2") (pintype "passive"))
      (node (ref "R21") (pin "2") (pinfunction "2_2") (pintype "passive"))
    )
    (net (code "111") (name "Net-(LED2-A)") (class "Default")
      (node (ref "LED2") (pin "2") (pinfunction "A_2") (pintype "passive"))
      (node (ref "R42") (pin "2") (pinfunction "2_2") (pintype "passive"))
    )
    (net (code "112") (name "Net-(LED3-A)") (class "Default")
      (node (ref "LED3") (pin "2") (pinfunction "A_2") (pintype "passive"))
      (node (ref "R45") (pin "2") (pinfunction "2_2") (pintype "passive"))
    )
    (net (code "113") (name "Net-(LED4-A)") (class "Default")
      (node (ref "LED4") (pin "2") (pinfunction "A_2") (pintype "passive"))
      (node (ref "R47") (pin "2") (pinfunction "2_2") (pintype "passive"))
    )
    (net (code "114") (name "Net-(LED5-A)") (class "Default")
      (node (ref "LED5") (pin "2") (pinfunction "A_2") (pintype "passive"))
      (node (ref "R48") (pin "2") (pinfunction "2_2") (pintype "passive"))
    )
    (net (code "115") (name "Net-(U2A-PC14)") (class "Default")
      (node (ref "C8") (pin "2") (pinfunction "2_2") (pintype "passive"))
      (node (ref "U2") (pin "8") (pinfunction "PC14_8") (pintype "passive"))
      (node (ref "X2") (pin "1") (pinfunction "1_1") (pintype "passive"))
    )
    (net (code "116") (name "Net-(U2A-PC15)") (class "Default")
      (node (ref "C9") (pin "2") (pinfunction "2_2") (pintype "passive"))
      (node (ref "U2") (pin "9") (pinfunction "PC15_9") (pintype "passive"))
      (node (ref "X2") (pin "2") (pinfunction "2_2") (pintype "passive"))
    )
    (net (code "117") (name "Net-(U2B-OSC_IN)") (class "Default")
      (node (ref "C6") (pin "1") (pinfunction "1_1") (pintype "passive"))
      (node (ref "U2") (pin "23") (pinfunction "OSC_IN_23") (pintype "passive"))
      (node (ref "X1") (pin "3") (pinfunction "3_3") (pintype "passive"))
    )
    (net (code "118") (name "Net-(U2B-OSC_OUT)") (class "Default")
      (node (ref "C7") (pin "1") (pinfunction "1_1") (pintype "passive"))
      (node (ref "U2") (pin "24") (pinfunction "OSC_OUT_24") (pintype "passive"))
      (node (ref "X1") (pin "1") (pinfunction "1_1") (pintype "passive"))
    )
    (net (code "119") (name "Net-(U2B-VCAP_1)") (class "Default")
      (node (ref "C11") (pin "2") (pinfunction "2_2") (pintype "passive"))
      (node (ref "U2") (pin "71") (pinfunction "VCAP_1_71") (pintype "passive"))
    )
    (net (code "120") (name "Net-(U2B-VCAP_2)") (class "Default")
      (node (ref "C10") (pin "2") (pinfunction "2_2") (pintype "passive"))
      (node (ref "U2") (pin "106") (pinfunction "VCAP_2_106") (pintype "passive"))
    )
    (net (code "121") (name "Vref") (class "Default")
      (node (ref "C16") (pin "2") (pinfunction "2_2") (pintype "passive"))
      (node (ref "L2") (pin "2") (pinfunction "2_2") (pintype "passive"))
      (node (ref "U2") (pin "32") (pinfunction "VREF+_32") (pintype "passive"))
    )
    (net (code "122") (name "unconnected-(CN3-Pad2)") (class "Default")
      (node (ref "CN3") (pin "2") (pinfunction "2_2") (pintype "passive"))
    )
    (net (code "123") (name "unconnected-(LG1-Pad0)") (class "Default")
      (node (ref "LG1") (pin "0") (pinfunction "0_0") (pintype "passive"))
    )
    (net (code "124") (name "unconnected-(LG1-Pad0)_1") (class "Default")
      (node (ref "LG1") (pin "0") (pinfunction "0_0") (pintype "passive"))
    )
    (net (code "125") (name "unconnected-(LG1-Pad0)_2") (class "Default")
      (node (ref "LG1") (pin "0") (pinfunction "0_0") (pintype "passive"))
    )
    (net (code "126") (name "unconnected-(LG1-Pad0)_3") (class "Default")
      (node (ref "LG1") (pin "0") (pinfunction "0_0") (pintype "passive"))
    )
    (net (code "127") (name "unconnected-(LG2-Pad0)") (class "Default")
      (node (ref "LG2") (pin "0") (pinfunction "0_0") (pintype "passive"))
    )
    (net (code "128") (name "unconnected-(LG2-Pad0)_1") (class "Default")
      (node (ref "LG2") (pin "0") (pinfunction "0_0") (pintype "passive"))
    )
    (net (code "129") (name "unconnected-(LG2-Pad0)_2") (class "Default")
      (node (ref "LG2") (pin "0") (pinfunction "0_0") (pintype "passive"))
    )
    (net (code "130") (name "unconnected-(LG2-Pad0)_3") (class "Default")
      (node (ref "LG2") (pin "0") (pinfunction "0_0") (pintype "passive"))
    )
    (net (code "131") (name "unconnected-(LG3-Pad0)") (class "Default")
      (node (ref "LG3") (pin "0") (pinfunction "0_0") (pintype "passive"))
    )
    (net (code "132") (name "unconnected-(LG3-Pad0)_1") (class "Default")
      (node (ref "LG3") (pin "0") (pinfunction "0_0") (pintype "passive"))
    )
    (net (code "133") (name "unconnected-(LG3-Pad0)_2") (class "Default")
      (node (ref "LG3") (pin "0") (pinfunction "0_0") (pintype "passive"))
    )
    (net (code "134") (name "unconnected-(LG3-Pad0)_3") (class "Default")
      (node (ref "LG3") (pin "0") (pinfunction "0_0") (pintype "passive"))
    )
    (net (code "135") (name "unconnected-(LG4-Pad0)") (class "Default")
      (node (ref "LG4") (pin "0") (pinfunction "0_0") (pintype "passive"))
    )
    (net (code "136") (name "unconnected-(LG4-Pad0)_1") (class "Default")
      (node (ref "LG4") (pin "0") (pinfunction "0_0") (pintype "passive"))
    )
    (net (code "137") (name "unconnected-(LG4-Pad0)_2") (class "Default")
      (node (ref "LG4") (pin "0") (pinfunction "0_0") (pintype "passive"))
    )
    (net (code "138") (name "unconnected-(LG4-Pad0)_3") (class "Default")
      (node (ref "LG4") (pin "0") (pinfunction "0_0") (pintype "passive"))
    )
    (net (code "139") (name "unconnected-(U2A-PA00-Pad34)") (class "Default")
      (node (ref "U2") (pin "34") (pinfunction "PA00_34") (pintype "passive"))
    )
    (net (code "140") (name "unconnected-(U2A-PA01-Pad35)") (class "Default")
      (node (ref "U2") (pin "35") (pinfunction "PA01_35") (pintype "passive"))
    )
    (net (code "141") (name "unconnected-(U2A-PB00-Pad46)") (class "Default")
      (node (ref "U2") (pin "46") (pinfunction "PB00_46") (pintype "passive"))
    )
    (net (code "142") (name "unconnected-(U2A-PB01-Pad47)") (class "Default")
      (node (ref "U2") (pin "47") (pinfunction "PB01_47") (pintype "passive"))
    )
    (net (code "143") (name "unconnected-(U2A-PB02-Pad48)") (class "Default")
      (node (ref "U2") (pin "48") (pinfunction "PB02_48") (pintype "passive"))
    )
    (net (code "144") (name "unconnected-(U2A-PB14-Pad75)") (class "Default")
      (node (ref "U2") (pin "75") (pinfunction "PB14_75") (pintype "passive"))
    )
    (net (code "145") (name "unconnected-(U2A-PC00-Pad26)") (class "Default")
      (node (ref "U2") (pin "26") (pinfunction "PC00_26") (pintype "passive"))
    )
    (net (code "146") (name "unconnected-(U2A-PC01-Pad27)") (class "Default")
      (node (ref "U2") (pin "27") (pinfunction "PC01_27") (pintype "passive"))
    )
    (net (code "147") (name "unconnected-(U2A-PC09-Pad99)") (class "Default")
      (node (ref "U2") (pin "99") (pinfunction "PC09_99") (pintype "passive"))
    )
    (net (code "148") (name "unconnected-(U2A-PC10-Pad111)") (class "Default")
      (node (ref "U2") (pin "111") (pinfunction "PC10_111") (pintype "passive"))
    )
    (net (code "149") (name "unconnected-(U2A-PC11-Pad112)") (class "Default")
      (node (ref "U2") (pin "112") (pinfunction "PC11_112") (pintype "passive"))
    )
    (net (code "150") (name "unconnected-(U2A-PC12-Pad113)") (class "Default")
      (node (ref "U2") (pin "113") (pinfunction "PC12_113") (pintype "passive"))
    )
    (net (code "151") (name "unconnected-(U2A-PC13-Pad7)") (class "Default")
      (node (ref "U2") (pin "7") (pinfunction "PC13_7") (pintype "passive"))
    )
    (net (code "152") (name "unconnected-(U2A-PD02-Pad116)") (class "Default")
      (node (ref "U2") (pin "116") (pinfunction "PD02_116") (pintype "passive"))
    )
    (net (code "153") (name "unconnected-(U2A-PD03-Pad117)") (class "Default")
      (node (ref "U2") (pin "117") (pinfunction "PD03_117") (pintype "passive"))
    )
    (net (code "154") (name "unconnected-(U2A-PD06-Pad122)") (class "Default")
      (node (ref "U2") (pin "122") (pinfunction "PD06_122") (pintype "passive"))
    )
    (net (code "155") (name "unconnected-(U2A-PF10-Pad22)") (class "Default")
      (node (ref "U2") (pin "22") (pinfunction "PF10_22") (pintype "passive"))
    )
    (net (code "156") (name "unconnected-(U2A-PF11-Pad49)") (class "Default")
      (node (ref "U2") (pin "49") (pinfunction "PF11_49") (pintype "passive"))
    )
    (net (code "157") (name "unconnected-(U2A-PG06-Pad91)") (class "Default")
      (node (ref "U2") (pin "91") (pinfunction "PG06_91") (pintype "passive"))
    )
    (net (code "158") (name "unconnected-(U2A-PG07-Pad92)") (class "Default")
      (node (ref "U2") (pin "92") (pinfunction "PG07_92") (pintype "passive"))
    )
    (net (code "159") (name "unconnected-(U2A-PG08-Pad93)") (class "Default")
      (node (ref "U2") (pin "93") (pinfunction "PG08_93") (pintype "passive"))
    )
    (net (code "160") (name "unconnected-(U2A-PG09-Pad124)") (class "Default")
      (node (ref "U2") (pin "124") (pinfunction "PG09_124") (pintype "passive"))
    )
    (net (code "161") (name "unconnected-(U2A-PG10-Pad125)") (class "Default")
      (node (ref "U2") (pin "125") (pinfunction "PG10_125") (pintype "passive"))
    )
    (net (code "162") (name "unconnected-(U2A-PG11-Pad126)") (class "Default")
      (node (ref "U2") (pin "126") (pinfunction "PG11_126") (pintype "passive"))
    )
    (net (code "163") (name "unconnected-(U2A-PG13-Pad128)") (class "Default")
      (node (ref "U2") (pin "128") (pinfunction "PG13_128") (pintype "passive"))
    )
    (net (code "164") (name "unconnected-(U2A-PG14-Pad129)") (class "Default")
      (node (ref "U2") (pin "129") (pinfunction "PG14_129") (pintype "passive"))
    )
    (net (code "165") (name "unconnected-(U2A-PG15-Pad132)") (class "Default")
      (node (ref "U2") (pin "132") (pinfunction "PG15_132") (pintype "passive"))
    )
  )
)
